# SCH_AVlabs_AV-GMK_MK_I_2024-01-18.net
KiCad netlist of a schematic drawn in EasyEDA
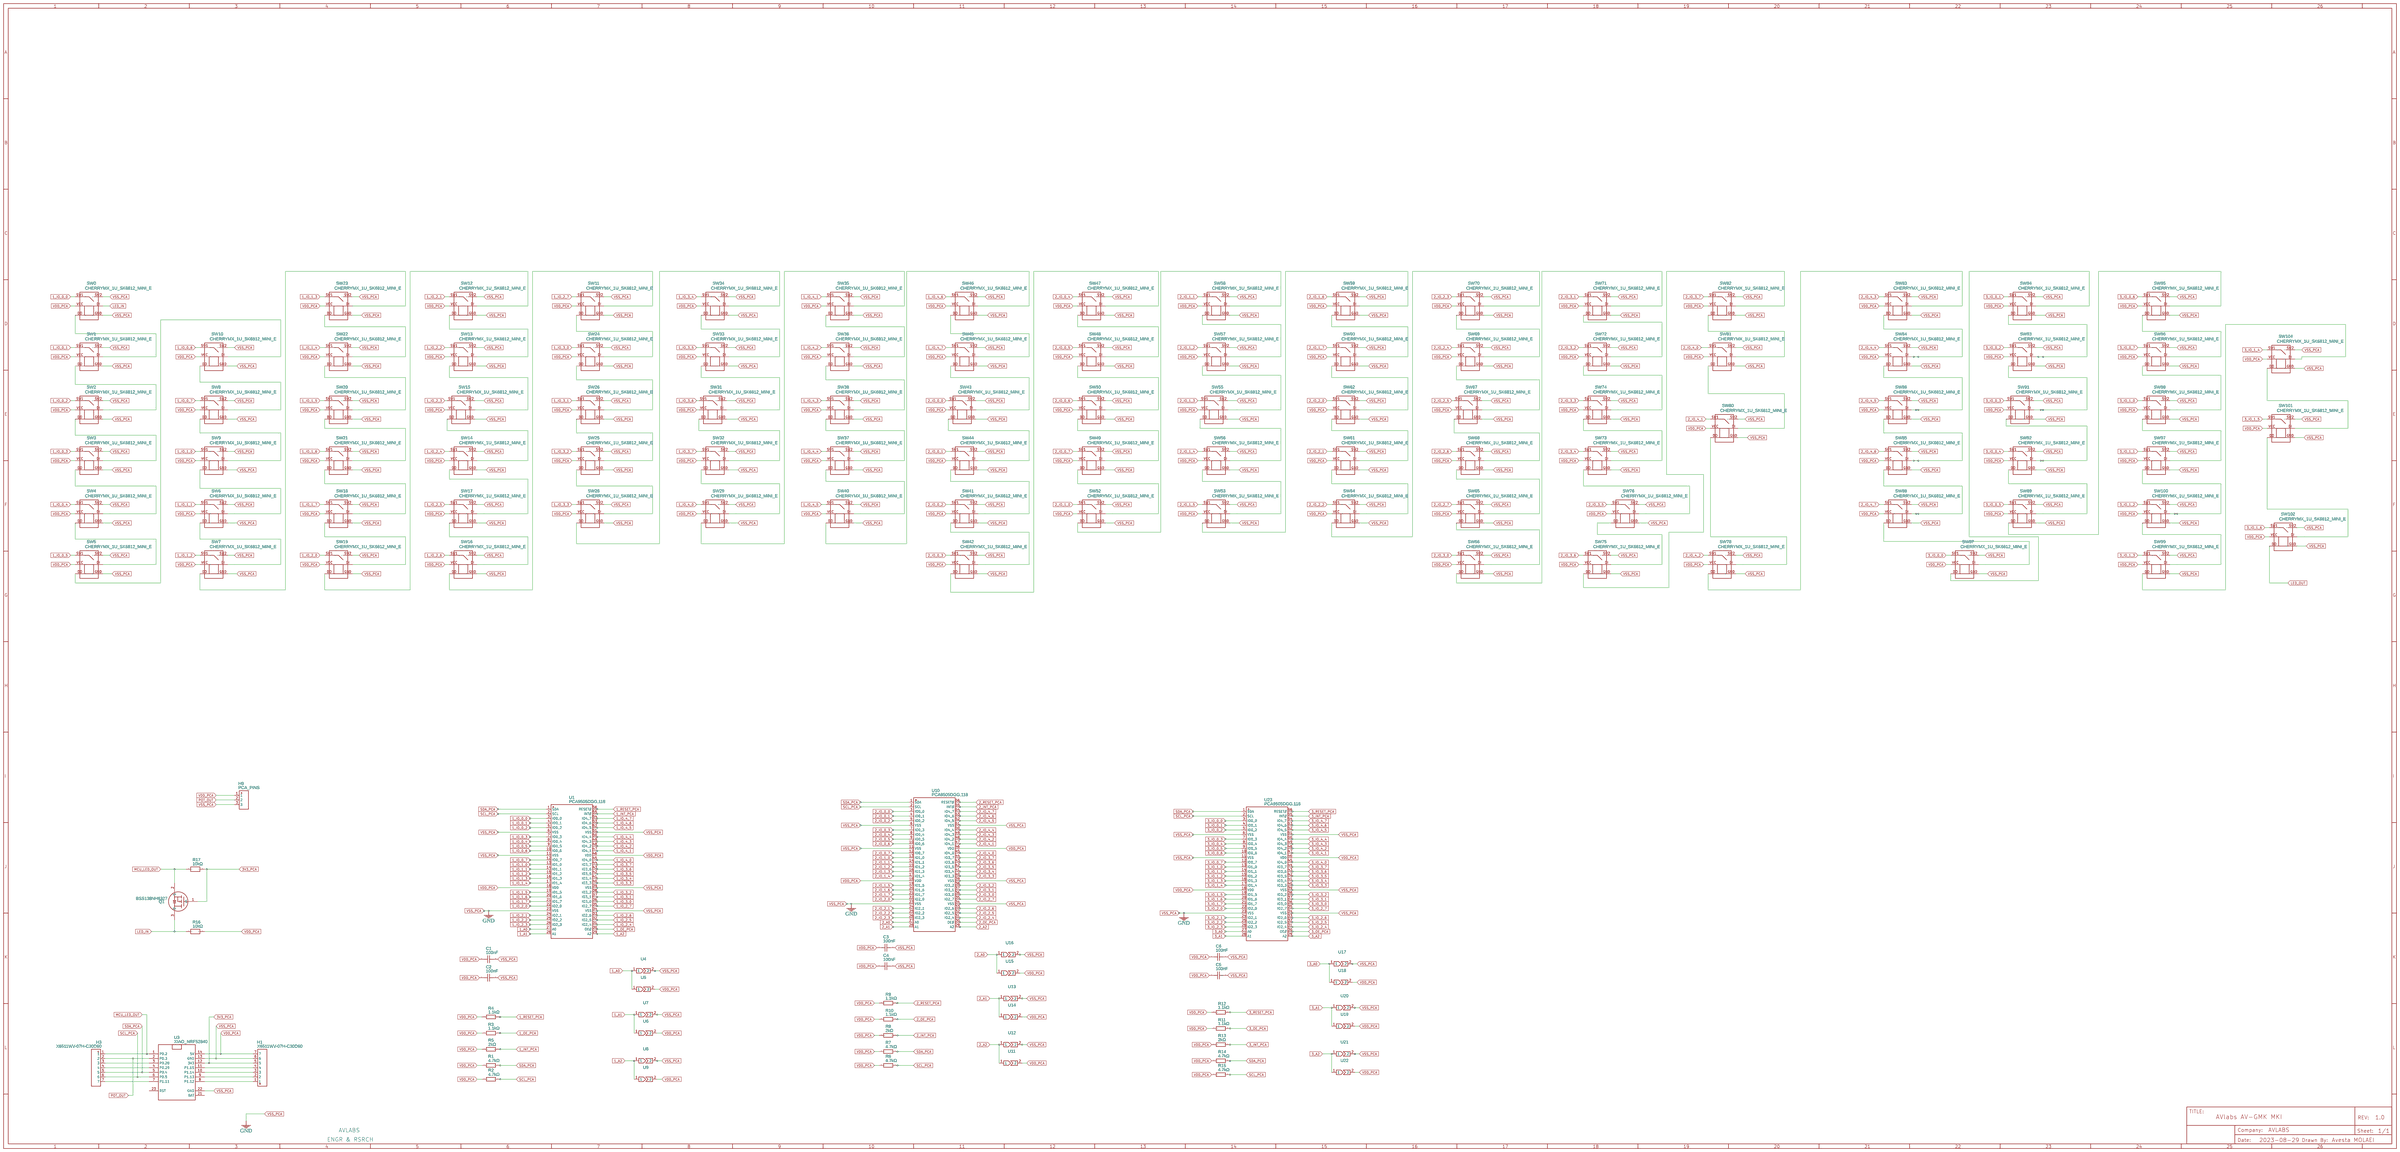
[diagram p0: schematic sheet]

(export (version "E")
  (design (tool "Eeschema 10.0.6"))
  (components
    (comp (ref "C1")
      (value "100nF")
      (fields
        (field (name "Manufacturer Part") "GRM21BR71H104KA01L")
        (field (name "Manufacturer") "muRata(村田)")
      )
      (libsource (lib "") (part "GRM21BR71H104KA01L"))
    )
    (comp (ref "C2")
      (value "100nF")
      (fields
        (field (name "Manufacturer Part") "GRM21BR71H104KA01L")
        (field (name "Manufacturer") "muRata(村田)")
      )
      (libsource (lib "") (part "GRM21BR71H104KA01L"))
    )
    (comp (ref "C3")
      (value "100nF")
      (fields
        (field (name "Manufacturer Part") "GRM21BR71H104KA01L")
        (field (name "Manufacturer") "muRata(村田)")
      )
      (libsource (lib "") (part "GRM21BR71H104KA01L"))
    )
    (comp (ref "C4")
      (value "100nF")
      (fields
        (field (name "Manufacturer Part") "GRM21BR71H104KA01L")
        (field (name "Manufacturer") "muRata(村田)")
      )
      (libsource (lib "") (part "GRM21BR71H104KA01L"))
    )
    (comp (ref "C5")
      (value "100nF")
      (fields
        (field (name "Manufacturer Part") "GRM21BR71H104KA01L")
        (field (name "Manufacturer") "muRata(村田)")
      )
      (libsource (lib "") (part "GRM21BR71H104KA01L"))
    )
    (comp (ref "C6")
      (value "100nF")
      (fields
        (field (name "Manufacturer Part") "GRM21BR71H104KA01L")
        (field (name "Manufacturer") "muRata(村田)")
      )
      (libsource (lib "") (part "GRM21BR71H104KA01L"))
    )
    (comp (ref "H1")
      (value "X6511WV-07H-C30D60")
      (fields (field (name "Manufacturer") "XKB Connectivity(中国星坤)"))
      (libsource (lib "") (part "X6511WV-07H-C30D60"))
    )
    (comp (ref "H3")
      (value "X6511WV-07H-C30D60")
      (fields (field (name "Manufacturer") "XKB Connectivity(中国星坤)"))
      (libsource (lib "") (part "X6511WV-07H-C30D60_1"))
    )
    (comp (ref "H9")
      (value "PCA_PINS")
      (fields
        (field (name "Manufacturer Part") "X6511WV-03H-C30D60")
        (field (name "Manufacturer") "XKB Connectivity(中国星坤)")
      )
      (libsource (lib "") (part "X6511WV-03H-C30D60"))
    )
    (comp (ref "Q1")
      (value "BSS138NH6327")
      (fields (field (name "Manufacturer") "Infineon(英飞凌)"))
      (libsource (lib "") (part "BSS138NH6327"))
    )
    (comp (ref "R1")
      (value "4.7kΩ")
      (fields (field (name "Manufacturer Part") "RN732ATTD4701B25") (field (name "Manufacturer") "KOA"))
      (libsource (lib "") (part "RN732ATTD4701B25"))
    )
    (comp (ref "R2")
      (value "4.7kΩ")
      (fields (field (name "Manufacturer Part") "RN732ATTD4701B25") (field (name "Manufacturer") "KOA"))
      (libsource (lib "") (part "RN732ATTD4701B25"))
    )
    (comp (ref "R3")
      (value "1.1kΩ")
      (fields (field (name "Manufacturer Part") "RN732ATTD1101B25") (field (name "Manufacturer") "KOA"))
      (libsource (lib "") (part "RN732ATTD1101B25"))
    )
    (comp (ref "R4")
      (value "1.1kΩ")
      (fields (field (name "Manufacturer Part") "RN732ATTD1101B25") (field (name "Manufacturer") "KOA"))
      (libsource (lib "") (part "RN732ATTD1101B25"))
    )
    (comp (ref "R5")
      (value "2kΩ")
      (fields (field (name "Manufacturer Part") "RN732ATTD2001B25") (field (name "Manufacturer") "KOA"))
      (libsource (lib "") (part "RN732ATTD2001B25"))
    )
    (comp (ref "R6")
      (value "4.7kΩ")
      (fields (field (name "Manufacturer Part") "RN732ATTD4701B25") (field (name "Manufacturer") "KOA"))
      (libsource (lib "") (part "RN732ATTD4701B25"))
    )
    (comp (ref "R7")
      (value "4.7kΩ")
      (fields (field (name "Manufacturer Part") "RN732ATTD4701B25") (field (name "Manufacturer") "KOA"))
      (libsource (lib "") (part "RN732ATTD4701B25"))
    )
    (comp (ref "R8")
      (value "2kΩ")
      (fields (field (name "Manufacturer Part") "RN732ATTD2001B25") (field (name "Manufacturer") "KOA"))
      (libsource (lib "") (part "RN732ATTD2001B25"))
    )
    (comp (ref "R9")
      (value "1.1kΩ")
      (fields (field (name "Manufacturer Part") "RN732ATTD1101B25") (field (name "Manufacturer") "KOA"))
      (libsource (lib "") (part "RN732ATTD1101B25"))
    )
    (comp (ref "R10")
      (value "1.1kΩ")
      (fields (field (name "Manufacturer Part") "RN732ATTD1101B25") (field (name "Manufacturer") "KOA"))
      (libsource (lib "") (part "RN732ATTD1101B25"))
    )
    (comp (ref "R11")
      (value "1.1kΩ")
      (fields (field (name "Manufacturer Part") "RN732ATTD1101B25") (field (name "Manufacturer") "KOA"))
      (libsource (lib "") (part "RN732ATTD1101B25"))
    )
    (comp (ref "R12")
      (value "1.1kΩ")
      (fields (field (name "Manufacturer Part") "RN732ATTD1101B25") (field (name "Manufacturer") "KOA"))
      (libsource (lib "") (part "RN732ATTD1101B25"))
    )
    (comp (ref "R13")
      (value "2kΩ")
      (fields (field (name "Manufacturer Part") "RN732ATTD2001B25") (field (name "Manufacturer") "KOA"))
      (libsource (lib "") (part "RN732ATTD2001B25"))
    )
    (comp (ref "R14")
      (value "4.7kΩ")
      (fields (field (name "Manufacturer Part") "RN732ATTD4701B25") (field (name "Manufacturer") "KOA"))
      (libsource (lib "") (part "RN732ATTD4701B25"))
    )
    (comp (ref "R15")
      (value "4.7kΩ")
      (fields (field (name "Manufacturer Part") "RN732ATTD4701B25") (field (name "Manufacturer") "KOA"))
      (libsource (lib "") (part "RN732ATTD4701B25"))
    )
    (comp (ref "R16")
      (value "10kΩ")
      (fields (field (name "Manufacturer Part") "RN732ATTD1002B10") (field (name "Manufacturer") "KOA"))
      (libsource (lib "") (part "RN732ATTD1002B10"))
    )
    (comp (ref "R17")
      (value "10kΩ")
      (fields (field (name "Manufacturer Part") "RN732ATTD1002B10") (field (name "Manufacturer") "KOA"))
      (libsource (lib "") (part "RN732ATTD1002B10"))
    )
    (comp (ref "SW0")
      (value "CHERRYMX_1U_SK6812_MINI_E")
      (libsource (lib "") (part "CHERRYMX_1U_SK6812_MINI_E"))
    )
    (comp (ref "SW1")
      (value "CHERRYMX_1U_SK6812_MINI_E")
      (libsource (lib "") (part "CHERRYMX_1U_SK6812_MINI_E"))
    )
    (comp (ref "SW2")
      (value "CHERRYMX_1U_SK6812_MINI_E")
      (libsource (lib "") (part "CHERRYMX_1U_SK6812_MINI_E"))
    )
    (comp (ref "SW3")
      (value "CHERRYMX_1U_SK6812_MINI_E")
      (libsource (lib "") (part "CHERRYMX_1U_SK6812_MINI_E"))
    )
    (comp (ref "SW4")
      (value "CHERRYMX_1U_SK6812_MINI_E")
      (libsource (lib "") (part "CHERRYMX_1U_SK6812_MINI_E"))
    )
    (comp (ref "SW5")
      (value "CHERRYMX_1U_SK6812_MINI_E")
      (libsource (lib "") (part "CHERRYMX_1U_SK6812_MINI_E"))
    )
    (comp (ref "SW6")
      (value "CHERRYMX_1U_SK6812_MINI_E")
      (libsource (lib "") (part "CHERRYMX_1U_SK6812_MINI_E"))
    )
    (comp (ref "SW7")
      (value "CHERRYMX_1U_SK6812_MINI_E")
      (libsource (lib "") (part "CHERRYMX_1U_SK6812_MINI_E"))
    )
    (comp (ref "SW8")
      (value "CHERRYMX_1U_SK6812_MINI_E")
      (libsource (lib "") (part "CHERRYMX_1U_SK6812_MINI_E"))
    )
    (comp (ref "SW9")
      (value "CHERRYMX_1U_SK6812_MINI_E")
      (libsource (lib "") (part "CHERRYMX_1U_SK6812_MINI_E"))
    )
    (comp (ref "SW10")
      (value "CHERRYMX_1U_SK6812_MINI_E")
      (libsource (lib "") (part "CHERRYMX_1U_SK6812_MINI_E"))
    )
    (comp (ref "SW11")
      (value "CHERRYMX_1U_SK6812_MINI_E")
      (libsource (lib "") (part "CHERRYMX_1U_SK6812_MINI_E"))
    )
    (comp (ref "SW12")
      (value "CHERRYMX_1U_SK6812_MINI_E")
      (libsource (lib "") (part "CHERRYMX_1U_SK6812_MINI_E"))
    )
    (comp (ref "SW13")
      (value "CHERRYMX_1U_SK6812_MINI_E")
      (libsource (lib "") (part "CHERRYMX_1U_SK6812_MINI_E"))
    )
    (comp (ref "SW14")
      (value "CHERRYMX_1U_SK6812_MINI_E")
      (libsource (lib "") (part "CHERRYMX_1U_SK6812_MINI_E"))
    )
    (comp (ref "SW15")
      (value "CHERRYMX_1U_SK6812_MINI_E")
      (libsource (lib "") (part "CHERRYMX_1U_SK6812_MINI_E"))
    )
    (comp (ref "SW16")
      (value "CHERRYMX_1U_SK6812_MINI_E")
      (libsource (lib "") (part "CHERRYMX_1U_SK6812_MINI_E"))
    )
    (comp (ref "SW17")
      (value "CHERRYMX_1U_SK6812_MINI_E")
      (libsource (lib "") (part "CHERRYMX_1U_SK6812_MINI_E"))
    )
    (comp (ref "SW18")
      (value "CHERRYMX_1U_SK6812_MINI_E")
      (libsource (lib "") (part "CHERRYMX_1U_SK6812_MINI_E"))
    )
    (comp (ref "SW19")
      (value "CHERRYMX_1U_SK6812_MINI_E")
      (libsource (lib "") (part "CHERRYMX_1U_SK6812_MINI_E"))
    )
    (comp (ref "SW20")
      (value "CHERRYMX_1U_SK6812_MINI_E")
      (libsource (lib "") (part "CHERRYMX_1U_SK6812_MINI_E"))
    )
    (comp (ref "SW21")
      (value "CHERRYMX_1U_SK6812_MINI_E")
      (libsource (lib "") (part "CHERRYMX_1U_SK6812_MINI_E"))
    )
    (comp (ref "SW22")
      (value "CHERRYMX_1U_SK6812_MINI_E")
      (libsource (lib "") (part "CHERRYMX_1U_SK6812_MINI_E"))
    )
    (comp (ref "SW23")
      (value "CHERRYMX_1U_SK6812_MINI_E")
      (libsource (lib "") (part "CHERRYMX_1U_SK6812_MINI_E"))
    )
    (comp (ref "SW24")
      (value "CHERRYMX_1U_SK6812_MINI_E")
      (libsource (lib "") (part "CHERRYMX_1U_SK6812_MINI_E"))
    )
    (comp (ref "SW25")
      (value "CHERRYMX_1U_SK6812_MINI_E")
      (libsource (lib "") (part "CHERRYMX_1U_SK6812_MINI_E"))
    )
    (comp (ref "SW26")
      (value "CHERRYMX_1U_SK6812_MINI_E")
      (libsource (lib "") (part "CHERRYMX_1U_SK6812_MINI_E"))
    )
    (comp (ref "SW28")
      (value "CHERRYMX_1U_SK6812_MINI_E")
      (libsource (lib "") (part "CHERRYMX_1U_SK6812_MINI_E"))
    )
    (comp (ref "SW29")
      (value "CHERRYMX_1U_SK6812_MINI_E")
      (libsource (lib "") (part "CHERRYMX_1U_SK6812_MINI_E"))
    )
    (comp (ref "SW31")
      (value "CHERRYMX_1U_SK6812_MINI_E")
      (libsource (lib "") (part "CHERRYMX_1U_SK6812_MINI_E"))
    )
    (comp (ref "SW32")
      (value "CHERRYMX_1U_SK6812_MINI_E")
      (libsource (lib "") (part "CHERRYMX_1U_SK6812_MINI_E"))
    )
    (comp (ref "SW33")
      (value "CHERRYMX_1U_SK6812_MINI_E")
      (libsource (lib "") (part "CHERRYMX_1U_SK6812_MINI_E"))
    )
    (comp (ref "SW34")
      (value "CHERRYMX_1U_SK6812_MINI_E")
      (libsource (lib "") (part "CHERRYMX_1U_SK6812_MINI_E"))
    )
    (comp (ref "SW35")
      (value "CHERRYMX_1U_SK6812_MINI_E")
      (libsource (lib "") (part "CHERRYMX_1U_SK6812_MINI_E"))
    )
    (comp (ref "SW36")
      (value "CHERRYMX_1U_SK6812_MINI_E")
      (libsource (lib "") (part "CHERRYMX_1U_SK6812_MINI_E"))
    )
    (comp (ref "SW37")
      (value "CHERRYMX_1U_SK6812_MINI_E")
      (libsource (lib "") (part "CHERRYMX_1U_SK6812_MINI_E"))
    )
    (comp (ref "SW38")
      (value "CHERRYMX_1U_SK6812_MINI_E")
      (libsource (lib "") (part "CHERRYMX_1U_SK6812_MINI_E"))
    )
    (comp (ref "SW40")
      (value "CHERRYMX_1U_SK6812_MINI_E")
      (libsource (lib "") (part "CHERRYMX_1U_SK6812_MINI_E"))
    )
    (comp (ref "SW41")
      (value "CHERRYMX_1U_SK6812_MINI_E")
      (libsource (lib "") (part "CHERRYMX_1U_SK6812_MINI_E"))
    )
    (comp (ref "SW42")
      (value "CHERRYMX_1U_SK6812_MINI_E")
      (libsource (lib "") (part "CHERRYMX_1U_SK6812_MINI_E"))
    )
    (comp (ref "SW43")
      (value "CHERRYMX_1U_SK6812_MINI_E")
      (libsource (lib "") (part "CHERRYMX_1U_SK6812_MINI_E"))
    )
    (comp (ref "SW44")
      (value "CHERRYMX_1U_SK6812_MINI_E")
      (libsource (lib "") (part "CHERRYMX_1U_SK6812_MINI_E"))
    )
    (comp (ref "SW45")
      (value "CHERRYMX_1U_SK6812_MINI_E")
      (libsource (lib "") (part "CHERRYMX_1U_SK6812_MINI_E"))
    )
    (comp (ref "SW46")
      (value "CHERRYMX_1U_SK6812_MINI_E")
      (libsource (lib "") (part "CHERRYMX_1U_SK6812_MINI_E"))
    )
    (comp (ref "SW47")
      (value "CHERRYMX_1U_SK6812_MINI_E")
      (libsource (lib "") (part "CHERRYMX_1U_SK6812_MINI_E"))
    )
    (comp (ref "SW48")
      (value "CHERRYMX_1U_SK6812_MINI_E")
      (libsource (lib "") (part "CHERRYMX_1U_SK6812_MINI_E"))
    )
    (comp (ref "SW49")
      (value "CHERRYMX_1U_SK6812_MINI_E")
      (libsource (lib "") (part "CHERRYMX_1U_SK6812_MINI_E"))
    )
    (comp (ref "SW50")
      (value "CHERRYMX_1U_SK6812_MINI_E")
      (libsource (lib "") (part "CHERRYMX_1U_SK6812_MINI_E"))
    )
    (comp (ref "SW52")
      (value "CHERRYMX_1U_SK6812_MINI_E")
      (libsource (lib "") (part "CHERRYMX_1U_SK6812_MINI_E"))
    )
    (comp (ref "SW53")
      (value "CHERRYMX_1U_SK6812_MINI_E")
      (libsource (lib "") (part "CHERRYMX_1U_SK6812_MINI_E"))
    )
    (comp (ref "SW55")
      (value "CHERRYMX_1U_SK6812_MINI_E")
      (libsource (lib "") (part "CHERRYMX_1U_SK6812_MINI_E"))
    )
    (comp (ref "SW56")
      (value "CHERRYMX_1U_SK6812_MINI_E")
      (libsource (lib "") (part "CHERRYMX_1U_SK6812_MINI_E"))
    )
    (comp (ref "SW57")
      (value "CHERRYMX_1U_SK6812_MINI_E")
      (libsource (lib "") (part "CHERRYMX_1U_SK6812_MINI_E"))
    )
    (comp (ref "SW58")
      (value "CHERRYMX_1U_SK6812_MINI_E")
      (libsource (lib "") (part "CHERRYMX_1U_SK6812_MINI_E"))
    )
    (comp (ref "SW59")
      (value "CHERRYMX_1U_SK6812_MINI_E")
      (libsource (lib "") (part "CHERRYMX_1U_SK6812_MINI_E"))
    )
    (comp (ref "SW60")
      (value "CHERRYMX_1U_SK6812_MINI_E")
      (libsource (lib "") (part "CHERRYMX_1U_SK6812_MINI_E"))
    )
    (comp (ref "SW61")
      (value "CHERRYMX_1U_SK6812_MINI_E")
      (libsource (lib "") (part "CHERRYMX_1U_SK6812_MINI_E"))
    )
    (comp (ref "SW62")
      (value "CHERRYMX_1U_SK6812_MINI_E")
      (libsource (lib "") (part "CHERRYMX_1U_SK6812_MINI_E"))
    )
    (comp (ref "SW64")
      (value "CHERRYMX_1U_SK6812_MINI_E")
      (libsource (lib "") (part "CHERRYMX_1U_SK6812_MINI_E"))
    )
    (comp (ref "SW65")
      (value "CHERRYMX_1U_SK6812_MINI_E")
      (libsource (lib "") (part "CHERRYMX_1U_SK6812_MINI_E"))
    )
    (comp (ref "SW66")
      (value "CHERRYMX_1U_SK6812_MINI_E")
      (libsource (lib "") (part "CHERRYMX_1U_SK6812_MINI_E"))
    )
    (comp (ref "SW67")
      (value "CHERRYMX_1U_SK6812_MINI_E")
      (libsource (lib "") (part "CHERRYMX_1U_SK6812_MINI_E"))
    )
    (comp (ref "SW68")
      (value "CHERRYMX_1U_SK6812_MINI_E")
      (libsource (lib "") (part "CHERRYMX_1U_SK6812_MINI_E"))
    )
    (comp (ref "SW69")
      (value "CHERRYMX_1U_SK6812_MINI_E")
      (libsource (lib "") (part "CHERRYMX_1U_SK6812_MINI_E"))
    )
    (comp (ref "SW70")
      (value "CHERRYMX_1U_SK6812_MINI_E")
      (libsource (lib "") (part "CHERRYMX_1U_SK6812_MINI_E"))
    )
    (comp (ref "SW71")
      (value "CHERRYMX_1U_SK6812_MINI_E")
      (libsource (lib "") (part "CHERRYMX_1U_SK6812_MINI_E"))
    )
    (comp (ref "SW72")
      (value "CHERRYMX_1U_SK6812_MINI_E")
      (libsource (lib "") (part "CHERRYMX_1U_SK6812_MINI_E"))
    )
    (comp (ref "SW73")
      (value "CHERRYMX_1U_SK6812_MINI_E")
      (libsource (lib "") (part "CHERRYMX_1U_SK6812_MINI_E"))
    )
    (comp (ref "SW74")
      (value "CHERRYMX_1U_SK6812_MINI_E")
      (libsource (lib "") (part "CHERRYMX_1U_SK6812_MINI_E"))
    )
    (comp (ref "SW75")
      (value "CHERRYMX_1U_SK6812_MINI_E")
      (libsource (lib "") (part "CHERRYMX_1U_SK6812_MINI_E"))
    )
    (comp (ref "SW76")
      (value "CHERRYMX_1U_SK6812_MINI_E")
      (libsource (lib "") (part "CHERRYMX_1U_SK6812_MINI_E"))
    )
    (comp (ref "SW78")
      (value "CHERRYMX_1U_SK6812_MINI_E")
      (libsource (lib "") (part "CHERRYMX_1U_SK6812_MINI_E"))
    )
    (comp (ref "SW80")
      (value "CHERRYMX_1U_SK6812_MINI_E")
      (libsource (lib "") (part "CHERRYMX_1U_SK6812_MINI_E"))
    )
    (comp (ref "SW81")
      (value "CHERRYMX_1U_SK6812_MINI_E")
      (libsource (lib "") (part "CHERRYMX_1U_SK6812_MINI_E"))
    )
    (comp (ref "SW82")
      (value "CHERRYMX_1U_SK6812_MINI_E")
      (libsource (lib "") (part "CHERRYMX_1U_SK6812_MINI_E"))
    )
    (comp (ref "SW83")
      (value "CHERRYMX_1U_SK6812_MINI_E")
      (libsource (lib "") (part "CHERRYMX_1U_SK6812_MINI_E"))
    )
    (comp (ref "SW84")
      (value "CHERRYMX_1U_SK6812_MINI_E")
      (libsource (lib "") (part "CHERRYMX_1U_SK6812_MINI_E"))
    )
    (comp (ref "SW85")
      (value "CHERRYMX_1U_SK6812_MINI_E")
      (libsource (lib "") (part "CHERRYMX_1U_SK6812_MINI_E"))
    )
    (comp (ref "SW86")
      (value "CHERRYMX_1U_SK6812_MINI_E")
      (libsource (lib "") (part "CHERRYMX_1U_SK6812_MINI_E"))
    )
    (comp (ref "SW87")
      (value "CHERRYMX_1U_SK6812_MINI_E")
      (libsource (lib "") (part "CHERRYMX_1U_SK6812_MINI_E"))
    )
    (comp (ref "SW88")
      (value "CHERRYMX_1U_SK6812_MINI_E")
      (libsource (lib "") (part "CHERRYMX_1U_SK6812_MINI_E"))
    )
    (comp (ref "SW89")
      (value "CHERRYMX_1U_SK6812_MINI_E")
      (libsource (lib "") (part "CHERRYMX_1U_SK6812_MINI_E"))
    )
    (comp (ref "SW91")
      (value "CHERRYMX_1U_SK6812_MINI_E")
      (libsource (lib "") (part "CHERRYMX_1U_SK6812_MINI_E"))
    )
    (comp (ref "SW92")
      (value "CHERRYMX_1U_SK6812_MINI_E")
      (libsource (lib "") (part "CHERRYMX_1U_SK6812_MINI_E"))
    )
    (comp (ref "SW93")
      (value "CHERRYMX_1U_SK6812_MINI_E")
      (libsource (lib "") (part "CHERRYMX_1U_SK6812_MINI_E"))
    )
    (comp (ref "SW94")
      (value "CHERRYMX_1U_SK6812_MINI_E")
      (libsource (lib "") (part "CHERRYMX_1U_SK6812_MINI_E"))
    )
    (comp (ref "SW95")
      (value "CHERRYMX_1U_SK6812_MINI_E")
      (libsource (lib "") (part "CHERRYMX_1U_SK6812_MINI_E"))
    )
    (comp (ref "SW96")
      (value "CHERRYMX_1U_SK6812_MINI_E")
      (libsource (lib "") (part "CHERRYMX_1U_SK6812_MINI_E"))
    )
    (comp (ref "SW97")
      (value "CHERRYMX_1U_SK6812_MINI_E")
      (libsource (lib "") (part "CHERRYMX_1U_SK6812_MINI_E"))
    )
    (comp (ref "SW98")
      (value "CHERRYMX_1U_SK6812_MINI_E")
      (libsource (lib "") (part "CHERRYMX_1U_SK6812_MINI_E"))
    )
    (comp (ref "SW99")
      (value "CHERRYMX_1U_SK6812_MINI_E")
      (libsource (lib "") (part "CHERRYMX_1U_SK6812_MINI_E"))
    )
    (comp (ref "SW100")
      (value "CHERRYMX_1U_SK6812_MINI_E")
      (libsource (lib "") (part "CHERRYMX_1U_SK6812_MINI_E"))
    )
    (comp (ref "SW101")
      (value "CHERRYMX_1U_SK6812_MINI_E")
      (libsource (lib "") (part "CHERRYMX_1U_SK6812_MINI_E"))
    )
    (comp (ref "SW102")
      (value "CHERRYMX_1U_SK6812_MINI_E")
      (libsource (lib "") (part "CHERRYMX_1U_SK6812_MINI_E"))
    )
    (comp (ref "SW104")
      (value "CHERRYMX_1U_SK6812_MINI_E")
      (libsource (lib "") (part "CHERRYMX_1U_SK6812_MINI_E"))
    )
    (comp (ref "U1")
      (value "PCA9505DGG,118")
      (fields (field (name "Manufacturer") "NXP(恩智浦)"))
      (libsource (lib "") (part "PCA9505DGG,118"))
    )
    (comp (ref "U3") (value "XIAO_NRF52840") (libsource (lib "") (part "XIAO_NRF52840")))
    (comp (ref "U4") (value "beautiful-solderbridge") (libsource (lib "") (part "beautiful-solderbridge")))
    (comp (ref "U5") (value "beautiful-solderbridge") (libsource (lib "") (part "beautiful-solderbridge")))
    (comp (ref "U6") (value "beautiful-solderbridge") (libsource (lib "") (part "beautiful-solderbridge")))
    (comp (ref "U7") (value "beautiful-solderbridge") (libsource (lib "") (part "beautiful-solderbridge")))
    (comp (ref "U8") (value "beautiful-solderbridge") (libsource (lib "") (part "beautiful-solderbridge")))
    (comp (ref "U9") (value "beautiful-solderbridge") (libsource (lib "") (part "beautiful-solderbridge")))
    (comp (ref "U10")
      (value "PCA9505DGG,118")
      (fields (field (name "Manufacturer") "NXP(恩智浦)"))
      (libsource (lib "") (part "PCA9505DGG,118"))
    )
    (comp (ref "U11") (value "beautiful-solderbridge") (libsource (lib "") (part "beautiful-solderbridge")))
    (comp (ref "U12") (value "beautiful-solderbridge") (libsource (lib "") (part "beautiful-solderbridge")))
    (comp (ref "U13") (value "beautiful-solderbridge") (libsource (lib "") (part "beautiful-solderbridge")))
    (comp (ref "U14") (value "beautiful-solderbridge") (libsource (lib "") (part "beautiful-solderbridge")))
    (comp (ref "U15") (value "beautiful-solderbridge") (libsource (lib "") (part "beautiful-solderbridge")))
    (comp (ref "U16") (value "beautiful-solderbridge") (libsource (lib "") (part "beautiful-solderbridge")))
    (comp (ref "U17") (value "beautiful-solderbridge") (libsource (lib "") (part "beautiful-solderbridge")))
    (comp (ref "U18") (value "beautiful-solderbridge") (libsource (lib "") (part "beautiful-solderbridge")))
    (comp (ref "U19") (value "beautiful-solderbridge") (libsource (lib "") (part "beautiful-solderbridge")))
    (comp (ref "U20") (value "beautiful-solderbridge") (libsource (lib "") (part "beautiful-solderbridge")))
    (comp (ref "U21") (value "beautiful-solderbridge") (libsource (lib "") (part "beautiful-solderbridge")))
    (comp (ref "U22") (value "beautiful-solderbridge") (libsource (lib "") (part "beautiful-solderbridge")))
    (comp (ref "U23")
      (value "PCA9505DGG,118")
      (fields (field (name "Manufacturer") "NXP(恩智浦)"))
      (libsource (lib "") (part "PCA9505DGG,118"))
    )
  )
  (nets
    (net (code "1") (name "1_A0") (class "Default")
      (node (ref "U1") (pin "27") (pinfunction "A0_27") (pintype "unspecified"))
      (node (ref "U4") (pin "1") (pinfunction "1_1") (pintype "unspecified"))
      (node (ref "U5") (pin "1") (pinfunction "1_1") (pintype "unspecified"))
    )
    (net (code "2") (name "1_A1") (class "Default")
      (node (ref "U1") (pin "28") (pinfunction "A1_28") (pintype "unspecified"))
      (node (ref "U6") (pin "1") (pinfunction "1_1") (pintype "unspecified"))
      (node (ref "U7") (pin "1") (pinfunction "1_1") (pintype "unspecified"))
    )
    (net (code "3") (name "1_A2") (class "Default")
      (node (ref "U1") (pin "29") (pinfunction "A2_29") (pintype "unspecified"))
      (node (ref "U8") (pin "1") (pinfunction "1_1") (pintype "unspecified"))
      (node (ref "U9") (pin "1") (pinfunction "1_1") (pintype "unspecified"))
    )
    (net (code "4") (name "1_INT_PCA") (class "Default")
      (node (ref "R5") (pin "2") (pinfunction "2_2") (pintype "unspecified"))
      (node (ref "U1") (pin "55") (pinfunction "INT#_55") (pintype "unspecified"))
    )
    (net (code "5") (name "1_IO_0_0") (class "Default")
      (node (ref "SW0") (pin "SW1") (pinfunction "SW1_SW1") (pintype "unspecified"))
      (node (ref "U1") (pin "3") (pinfunction "IO0_0_3") (pintype "unspecified"))
    )
    (net (code "6") (name "1_IO_0_1") (class "Default")
      (node (ref "SW1") (pin "SW1") (pinfunction "SW1_SW1") (pintype "unspecified"))
      (node (ref "U1") (pin "4") (pinfunction "IO0_1_4") (pintype "unspecified"))
    )
    (net (code "7") (name "1_IO_0_2") (class "Default")
      (node (ref "SW2") (pin "SW1") (pinfunction "SW1_SW1") (pintype "unspecified"))
      (node (ref "U1") (pin "5") (pinfunction "IO0_2_5") (pintype "unspecified"))
    )
    (net (code "8") (name "1_IO_0_3") (class "Default")
      (node (ref "SW3") (pin "SW1") (pinfunction "SW1_SW1") (pintype "unspecified"))
      (node (ref "U1") (pin "7") (pinfunction "IO0_3_7") (pintype "unspecified"))
    )
    (net (code "9") (name "1_IO_0_4") (class "Default")
      (node (ref "SW4") (pin "SW1") (pinfunction "SW1_SW1") (pintype "unspecified"))
      (node (ref "U1") (pin "8") (pinfunction "IO0_4_8") (pintype "unspecified"))
    )
    (net (code "10") (name "1_IO_0_5") (class "Default")
      (node (ref "SW5") (pin "SW1") (pinfunction "SW1_SW1") (pintype "unspecified"))
      (node (ref "U1") (pin "9") (pinfunction "IO0_5_9") (pintype "unspecified"))
    )
    (net (code "11") (name "1_IO_0_6") (class "Default")
      (node (ref "SW10") (pin "SW1") (pinfunction "SW1_SW1") (pintype "unspecified"))
      (node (ref "U1") (pin "10") (pinfunction "IO0_6_10") (pintype "unspecified"))
    )
    (net (code "12") (name "1_IO_0_7") (class "Default")
      (node (ref "SW8") (pin "SW1") (pinfunction "SW1_SW1") (pintype "unspecified"))
      (node (ref "U1") (pin "12") (pinfunction "IO0_7_12") (pintype "unspecified"))
    )
    (net (code "13") (name "1_IO_1_0") (class "Default")
      (node (ref "SW9") (pin "SW1") (pinfunction "SW1_SW1") (pintype "unspecified"))
      (node (ref "U1") (pin "13") (pinfunction "IO1_0_13") (pintype "unspecified"))
    )
    (net (code "14") (name "1_IO_1_1") (class "Default")
      (node (ref "SW6") (pin "SW1") (pinfunction "SW1_SW1") (pintype "unspecified"))
      (node (ref "U1") (pin "14") (pinfunction "IO1_1_14") (pintype "unspecified"))
    )
    (net (code "15") (name "1_IO_1_2") (class "Default")
      (node (ref "SW7") (pin "SW1") (pinfunction "SW1_SW1") (pintype "unspecified"))
      (node (ref "U1") (pin "15") (pinfunction "IO1_2_15") (pintype "unspecified"))
    )
    (net (code "16") (name "1_IO_1_3") (class "Default")
      (node (ref "SW23") (pin "SW1") (pinfunction "SW1_SW1") (pintype "unspecified"))
      (node (ref "U1") (pin "16") (pinfunction "IO1_3_16") (pintype "unspecified"))
    )
    (net (code "17") (name "1_IO_1_4") (class "Default")
      (node (ref "SW22") (pin "SW1") (pinfunction "SW1_SW1") (pintype "unspecified"))
      (node (ref "U1") (pin "17") (pinfunction "IO1_4_17") (pintype "unspecified"))
    )
    (net (code "18") (name "1_IO_1_5") (class "Default")
      (node (ref "SW20") (pin "SW1") (pinfunction "SW1_SW1") (pintype "unspecified"))
      (node (ref "U1") (pin "19") (pinfunction "IO1_5_19") (pintype "unspecified"))
    )
    (net (code "19") (name "1_IO_1_6") (class "Default")
      (node (ref "SW21") (pin "SW1") (pinfunction "SW1_SW1") (pintype "unspecified"))
      (node (ref "U1") (pin "20") (pinfunction "IO1_6_20") (pintype "unspecified"))
    )
    (net (code "20") (name "1_IO_1_7") (class "Default")
      (node (ref "SW18") (pin "SW1") (pinfunction "SW1_SW1") (pintype "unspecified"))
      (node (ref "U1") (pin "21") (pinfunction "IO1_7_21") (pintype "unspecified"))
    )
    (net (code "21") (name "1_IO_2_0") (class "Default")
      (node (ref "SW19") (pin "SW1") (pinfunction "SW1_SW1") (pintype "unspecified"))
      (node (ref "U1") (pin "22") (pinfunction "IO2_0_22") (pintype "unspecified"))
    )
    (net (code "22") (name "1_IO_2_1") (class "Default")
      (node (ref "SW12") (pin "SW1") (pinfunction "SW1_SW1") (pintype "unspecified"))
      (node (ref "U1") (pin "24") (pinfunction "IO2_1_24") (pintype "unspecified"))
    )
    (net (code "23") (name "1_IO_2_2") (class "Default")
      (node (ref "SW13") (pin "SW1") (pinfunction "SW1_SW1") (pintype "unspecified"))
      (node (ref "U1") (pin "25") (pinfunction "IO2_2_25") (pintype "unspecified"))
    )
    (net (code "24") (name "1_IO_2_3") (class "Default")
      (node (ref "SW15") (pin "SW1") (pinfunction "SW1_SW1") (pintype "unspecified"))
      (node (ref "U1") (pin "26") (pinfunction "IO2_3_26") (pintype "unspecified"))
    )
    (net (code "25") (name "1_IO_2_4") (class "Default")
      (node (ref "SW14") (pin "SW1") (pinfunction "SW1_SW1") (pintype "unspecified"))
      (node (ref "U1") (pin "31") (pinfunction "IO2_4_31") (pintype "unspecified"))
    )
    (net (code "26") (name "1_IO_2_5") (class "Default")
      (node (ref "SW17") (pin "SW1") (pinfunction "SW1_SW1") (pintype "unspecified"))
      (node (ref "U1") (pin "32") (pinfunction "IO2_5_32") (pintype "unspecified"))
    )
    (net (code "27") (name "1_IO_2_6") (class "Default")
      (node (ref "SW16") (pin "SW1") (pinfunction "SW1_SW1") (pintype "unspecified"))
      (node (ref "U1") (pin "33") (pinfunction "IO2_6_33") (pintype "unspecified"))
    )
    (net (code "28") (name "1_IO_2_7") (class "Default")
      (node (ref "SW11") (pin "SW1") (pinfunction "SW1_SW1") (pintype "unspecified"))
      (node (ref "U1") (pin "35") (pinfunction "IO2_7_35") (pintype "unspecified"))
    )
    (net (code "29") (name "1_IO_3_0") (class "Default")
      (node (ref "SW24") (pin "SW1") (pinfunction "SW1_SW1") (pintype "unspecified"))
      (node (ref "U1") (pin "36") (pinfunction "IO3_0_36") (pintype "unspecified"))
    )
    (net (code "30") (name "1_IO_3_1") (class "Default")
      (node (ref "SW26") (pin "SW1") (pinfunction "SW1_SW1") (pintype "unspecified"))
      (node (ref "U1") (pin "37") (pinfunction "IO3_1_37") (pintype "unspecified"))
    )
    (net (code "31") (name "1_IO_3_2") (class "Default")
      (node (ref "SW25") (pin "SW1") (pinfunction "SW1_SW1") (pintype "unspecified"))
      (node (ref "U1") (pin "38") (pinfunction "IO3_2_38") (pintype "unspecified"))
    )
    (net (code "32") (name "1_IO_3_3") (class "Default")
      (node (ref "SW28") (pin "SW1") (pinfunction "SW1_SW1") (pintype "unspecified"))
      (node (ref "U1") (pin "40") (pinfunction "IO3_3_40") (pintype "unspecified"))
    )
    (net (code "33") (name "1_IO_3_4") (class "Default")
      (node (ref "SW34") (pin "SW1") (pinfunction "SW1_SW1") (pintype "unspecified"))
      (node (ref "U1") (pin "41") (pinfunction "IO3_4_41") (pintype "unspecified"))
    )
    (net (code "34") (name "1_IO_3_5") (class "Default")
      (node (ref "SW33") (pin "SW1") (pinfunction "SW1_SW1") (pintype "unspecified"))
      (node (ref "U1") (pin "42") (pinfunction "IO3_5_42") (pintype "unspecified"))
    )
    (net (code "35") (name "1_IO_3_6") (class "Default")
      (node (ref "SW31") (pin "SW1") (pinfunction "SW1_SW1") (pintype "unspecified"))
      (node (ref "U1") (pin "43") (pinfunction "IO3_6_43") (pintype "unspecified"))
    )
    (net (code "36") (name "1_IO_3_7") (class "Default")
      (node (ref "SW32") (pin "SW1") (pinfunction "SW1_SW1") (pintype "unspecified"))
      (node (ref "U1") (pin "44") (pinfunction "IO3_7_44") (pintype "unspecified"))
    )
    (net (code "37") (name "1_IO_4_0") (class "Default")
      (node (ref "SW29") (pin "SW1") (pinfunction "SW1_SW1") (pintype "unspecified"))
      (node (ref "U1") (pin "45") (pinfunction "IO4_0_45") (pintype "unspecified"))
    )
    (net (code "38") (name "1_IO_4_1") (class "Default")
      (node (ref "SW35") (pin "SW1") (pinfunction "SW1_SW1") (pintype "unspecified"))
      (node (ref "U1") (pin "47") (pinfunction "IO4_1_47") (pintype "unspecified"))
    )
    (net (code "39") (name "1_IO_4_2") (class "Default")
      (node (ref "SW36") (pin "SW1") (pinfunction "SW1_SW1") (pintype "unspecified"))
      (node (ref "U1") (pin "48") (pinfunction "IO4_2_48") (pintype "unspecified"))
    )
    (net (code "40") (name "1_IO_4_3") (class "Default")
      (node (ref "SW38") (pin "SW1") (pinfunction "SW1_SW1") (pintype "unspecified"))
      (node (ref "U1") (pin "49") (pinfunction "IO4_3_49") (pintype "unspecified"))
    )
    (net (code "41") (name "1_IO_4_4") (class "Default")
      (node (ref "SW37") (pin "SW1") (pinfunction "SW1_SW1") (pintype "unspecified"))
      (node (ref "U1") (pin "50") (pinfunction "IO4_4_50") (pintype "unspecified"))
    )
    (net (code "42") (name "1_IO_4_5") (class "Default")
      (node (ref "SW40") (pin "SW1") (pinfunction "SW1_SW1") (pintype "unspecified"))
      (node (ref "U1") (pin "52") (pinfunction "IO4_5_52") (pintype "unspecified"))
    )
    (net (code "43") (name "1_IO_4_6") (class "Default")
      (node (ref "SW46") (pin "SW1") (pinfunction "SW1_SW1") (pintype "unspecified"))
      (node (ref "U1") (pin "53") (pinfunction "IO4_6_53") (pintype "unspecified"))
    )
    (net (code "44") (name "1_IO_4_7") (class "Default")
      (node (ref "SW45") (pin "SW1") (pinfunction "SW1_SW1") (pintype "unspecified"))
      (node (ref "U1") (pin "54") (pinfunction "IO4_7_54") (pintype "unspecified"))
    )
    (net (code "45") (name "1_OE_PCA") (class "Default")
      (node (ref "R3") (pin "2") (pinfunction "2_2") (pintype "unspecified"))
      (node (ref "U1") (pin "30") (pinfunction "OE#_30") (pintype "unspecified"))
    )
    (net (code "46") (name "1_RESET_PCA") (class "Default")
      (node (ref "R4") (pin "2") (pinfunction "2_2") (pintype "unspecified"))
      (node (ref "U1") (pin "56") (pinfunction "RESET#_56") (pintype "unspecified"))
    )
    (net (code "47") (name "2_A0") (class "Default")
      (node (ref "U10") (pin "27") (pinfunction "A0_27") (pintype "unspecified"))
      (node (ref "U15") (pin "1") (pinfunction "1_1") (pintype "unspecified"))
      (node (ref "U16") (pin "1") (pinfunction "1_1") (pintype "unspecified"))
    )
    (net (code "48") (name "2_A1") (class "Default")
      (node (ref "U10") (pin "28") (pinfunction "A1_28") (pintype "unspecified"))
      (node (ref "U13") (pin "1") (pinfunction "1_1") (pintype "unspecified"))
      (node (ref "U14") (pin "1") (pinfunction "1_1") (pintype "unspecified"))
    )
    (net (code "49") (name "2_A2") (class "Default")
      (node (ref "U10") (pin "29") (pinfunction "A2_29") (pintype "unspecified"))
      (node (ref "U11") (pin "1") (pinfunction "1_1") (pintype "unspecified"))
      (node (ref "U12") (pin "1") (pinfunction "1_1") (pintype "unspecified"))
    )
    (net (code "50") (name "2_INT_PCA") (class "Default")
      (node (ref "R8") (pin "2") (pinfunction "2_2") (pintype "unspecified"))
      (node (ref "U10") (pin "55") (pinfunction "INT#_55") (pintype "unspecified"))
    )
    (net (code "51") (name "2_IO_0_0") (class "Default")
      (node (ref "SW43") (pin "SW1") (pinfunction "SW1_SW1") (pintype "unspecified"))
      (node (ref "U10") (pin "3") (pinfunction "IO0_0_3") (pintype "unspecified"))
    )
    (net (code "52") (name "2_IO_0_1") (class "Default")
      (node (ref "SW44") (pin "SW1") (pinfunction "SW1_SW1") (pintype "unspecified"))
      (node (ref "U10") (pin "4") (pinfunction "IO0_1_4") (pintype "unspecified"))
    )
    (net (code "53") (name "2_IO_0_2") (class "Default")
      (node (ref "SW41") (pin "SW1") (pinfunction "SW1_SW1") (pintype "unspecified"))
      (node (ref "U10") (pin "5") (pinfunction "IO0_2_5") (pintype "unspecified"))
    )
    (net (code "54") (name "2_IO_0_3") (class "Default")
      (node (ref "SW42") (pin "SW1") (pinfunction "SW1_SW1") (pintype "unspecified"))
      (node (ref "U10") (pin "7") (pinfunction "IO0_3_7") (pintype "unspecified"))
    )
    (net (code "55") (name "2_IO_0_4") (class "Default")
      (node (ref "SW47") (pin "SW1") (pinfunction "SW1_SW1") (pintype "unspecified"))
      (node (ref "U10") (pin "8") (pinfunction "IO0_4_8") (pintype "unspecified"))
    )
    (net (code "56") (name "2_IO_0_5") (class "Default")
      (node (ref "SW48") (pin "SW1") (pinfunction "SW1_SW1") (pintype "unspecified"))
      (node (ref "U10") (pin "9") (pinfunction "IO0_5_9") (pintype "unspecified"))
    )
    (net (code "57") (name "2_IO_0_6") (class "Default")
      (node (ref "SW50") (pin "SW1") (pinfunction "SW1_SW1") (pintype "unspecified"))
      (node (ref "U10") (pin "10") (pinfunction "IO0_6_10") (pintype "unspecified"))
    )
    (net (code "58") (name "2_IO_0_7") (class "Default")
      (node (ref "SW49") (pin "SW1") (pinfunction "SW1_SW1") (pintype "unspecified"))
      (node (ref "U10") (pin "12") (pinfunction "IO0_7_12") (pintype "unspecified"))
    )
    (net (code "59") (name "2_IO_1_0") (class "Default")
      (node (ref "SW52") (pin "SW1") (pinfunction "SW1_SW1") (pintype "unspecified"))
      (node (ref "U10") (pin "13") (pinfunction "IO1_0_13") (pintype "unspecified"))
    )
    (net (code "60") (name "2_IO_1_1") (class "Default")
      (node (ref "SW58") (pin "SW1") (pinfunction "SW1_SW1") (pintype "unspecified"))
      (node (ref "U10") (pin "14") (pinfunction "IO1_1_14") (pintype "unspecified"))
    )
    (net (code "61") (name "2_IO_1_2") (class "Default")
      (node (ref "SW57") (pin "SW1") (pinfunction "SW1_SW1") (pintype "unspecified"))
      (node (ref "U10") (pin "15") (pinfunction "IO1_2_15") (pintype "unspecified"))
    )
    (net (code "62") (name "2_IO_1_3") (class "Default")
      (node (ref "SW55") (pin "SW1") (pinfunction "SW1_SW1") (pintype "unspecified"))
      (node (ref "U10") (pin "16") (pinfunction "IO1_3_16") (pintype "unspecified"))
    )
    (net (code "63") (name "2_IO_1_4") (class "Default")
      (node (ref "SW56") (pin "SW1") (pinfunction "SW1_SW1") (pintype "unspecified"))
      (node (ref "U10") (pin "17") (pinfunction "IO1_4_17") (pintype "unspecified"))
    )
    (net (code "64") (name "2_IO_1_5") (class "Default")
      (node (ref "SW53") (pin "SW1") (pinfunction "SW1_SW1") (pintype "unspecified"))
      (node (ref "U10") (pin "19") (pinfunction "IO1_5_19") (pintype "unspecified"))
    )
    (net (code "65") (name "2_IO_1_6") (class "Default")
      (node (ref "SW59") (pin "SW1") (pinfunction "SW1_SW1") (pintype "unspecified"))
      (node (ref "U10") (pin "20") (pinfunction "IO1_6_20") (pintype "unspecified"))
    )
    (net (code "66") (name "2_IO_1_7") (class "Default")
      (node (ref "SW60") (pin "SW1") (pinfunction "SW1_SW1") (pintype "unspecified"))
      (node (ref "U10") (pin "21") (pinfunction "IO1_7_21") (pintype "unspecified"))
    )
    (net (code "67") (name "2_IO_2_0") (class "Default")
      (node (ref "SW62") (pin "SW1") (pinfunction "SW1_SW1") (pintype "unspecified"))
      (node (ref "U10") (pin "22") (pinfunction "IO2_0_22") (pintype "unspecified"))
    )
    (net (code "68") (name "2_IO_2_1") (class "Default")
      (node (ref "SW61") (pin "SW1") (pinfunction "SW1_SW1") (pintype "unspecified"))
      (node (ref "U10") (pin "24") (pinfunction "IO2_1_24") (pintype "unspecified"))
    )
    (net (code "69") (name "2_IO_2_2") (class "Default")
      (node (ref "SW64") (pin "SW1") (pinfunction "SW1_SW1") (pintype "unspecified"))
      (node (ref "U10") (pin "25") (pinfunction "IO2_2_25") (pintype "unspecified"))
    )
    (net (code "70") (name "2_IO_2_3") (class "Default")
      (node (ref "SW70") (pin "SW1") (pinfunction "SW1_SW1") (pintype "unspecified"))
      (node (ref "U10") (pin "26") (pinfunction "IO2_3_26") (pintype "unspecified"))
    )
    (net (code "71") (name "2_IO_2_4") (class "Default")
      (node (ref "SW69") (pin "SW1") (pinfunction "SW1_SW1") (pintype "unspecified"))
      (node (ref "U10") (pin "31") (pinfunction "IO2_4_31") (pintype "unspecified"))
    )
    (net (code "72") (name "2_IO_2_5") (class "Default")
      (node (ref "SW67") (pin "SW1") (pinfunction "SW1_SW1") (pintype "unspecified"))
      (node (ref "U10") (pin "32") (pinfunction "IO2_5_32") (pintype "unspecified"))
    )
    (net (code "73") (name "2_IO_2_6") (class "Default")
      (node (ref "SW68") (pin "SW1") (pinfunction "SW1_SW1") (pintype "unspecified"))
      (node (ref "U10") (pin "33") (pinfunction "IO2_6_33") (pintype "unspecified"))
    )
    (net (code "74") (name "2_IO_2_7") (class "Default")
      (node (ref "SW65") (pin "SW1") (pinfunction "SW1_SW1") (pintype "unspecified"))
      (node (ref "U10") (pin "35") (pinfunction "IO2_7_35") (pintype "unspecified"))
    )
    (net (code "75") (name "2_IO_3_0") (class "Default")
      (node (ref "SW66") (pin "SW1") (pinfunction "SW1_SW1") (pintype "unspecified"))
      (node (ref "U10") (pin "36") (pinfunction "IO3_0_36") (pintype "unspecified"))
    )
    (net (code "76") (name "2_IO_3_1") (class "Default")
      (node (ref "SW71") (pin "SW1") (pinfunction "SW1_SW1") (pintype "unspecified"))
      (node (ref "U10") (pin "37") (pinfunction "IO3_1_37") (pintype "unspecified"))
    )
    (net (code "77") (name "2_IO_3_2") (class "Default")
      (node (ref "SW72") (pin "SW1") (pinfunction "SW1_SW1") (pintype "unspecified"))
      (node (ref "U10") (pin "38") (pinfunction "IO3_2_38") (pintype "unspecified"))
    )
    (net (code "78") (name "2_IO_3_3") (class "Default")
      (node (ref "SW74") (pin "SW1") (pinfunction "SW1_SW1") (pintype "unspecified"))
      (node (ref "U10") (pin "40") (pinfunction "IO3_3_40") (pintype "unspecified"))
    )
    (net (code "79") (name "2_IO_3_4") (class "Default")
      (node (ref "SW73") (pin "SW1") (pinfunction "SW1_SW1") (pintype "unspecified"))
      (node (ref "U10") (pin "41") (pinfunction "IO3_4_41") (pintype "unspecified"))
    )
    (net (code "80") (name "2_IO_3_5") (class "Default")
      (node (ref "SW76") (pin "SW1") (pinfunction "SW1_SW1") (pintype "unspecified"))
      (node (ref "U10") (pin "42") (pinfunction "IO3_5_42") (pintype "unspecified"))
    )
    (net (code "81") (name "2_IO_3_6") (class "Default")
      (node (ref "SW75") (pin "SW1") (pinfunction "SW1_SW1") (pintype "unspecified"))
      (node (ref "U10") (pin "43") (pinfunction "IO3_6_43") (pintype "unspecified"))
    )
    (net (code "82") (name "2_IO_3_7") (class "Default")
      (node (ref "SW82") (pin "SW1") (pinfunction "SW1_SW1") (pintype "unspecified"))
      (node (ref "U10") (pin "44") (pinfunction "IO3_7_44") (pintype "unspecified"))
    )
    (net (code "83") (name "2_IO_4_0") (class "Default")
      (node (ref "SW81") (pin "SW1") (pinfunction "SW1_SW1") (pintype "unspecified"))
      (node (ref "U10") (pin "45") (pinfunction "IO4_0_45") (pintype "unspecified"))
    )
    (net (code "84") (name "2_IO_4_1") (class "Default")
      (node (ref "SW80") (pin "SW1") (pinfunction "SW1_SW1") (pintype "unspecified"))
      (node (ref "U10") (pin "47") (pinfunction "IO4_1_47") (pintype "unspecified"))
    )
    (net (code "85") (name "2_IO_4_2") (class "Default")
      (node (ref "SW78") (pin "SW1") (pinfunction "SW1_SW1") (pintype "unspecified"))
      (node (ref "U10") (pin "48") (pinfunction "IO4_2_48") (pintype "unspecified"))
    )
    (net (code "86") (name "2_IO_4_3") (class "Default")
      (node (ref "SW83") (pin "SW1") (pinfunction "SW1_SW1") (pintype "unspecified"))
      (node (ref "U10") (pin "49") (pinfunction "IO4_3_49") (pintype "unspecified"))
    )
    (net (code "87") (name "2_IO_4_4") (class "Default")
      (node (ref "SW84") (pin "SW1") (pinfunction "SW1_SW1") (pintype "unspecified"))
      (node (ref "U10") (pin "50") (pinfunction "IO4_4_50") (pintype "unspecified"))
    )
    (net (code "88") (name "2_IO_4_5") (class "Default")
      (node (ref "SW86") (pin "SW1") (pinfunction "SW1_SW1") (pintype "unspecified"))
      (node (ref "U10") (pin "52") (pinfunction "IO4_5_52") (pintype "unspecified"))
    )
    (net (code "89") (name "2_IO_4_6") (class "Default")
      (node (ref "SW85") (pin "SW1") (pinfunction "SW1_SW1") (pintype "unspecified"))
      (node (ref "U10") (pin "53") (pinfunction "IO4_6_53") (pintype "unspecified"))
    )
    (net (code "90") (name "2_IO_4_7") (class "Default")
      (node (ref "SW88") (pin "SW1") (pinfunction "SW1_SW1") (pintype "unspecified"))
      (node (ref "U10") (pin "54") (pinfunction "IO4_7_54") (pintype "unspecified"))
    )
    (net (code "91") (name "2_OE_PCA") (class "Default")
      (node (ref "R10") (pin "2") (pinfunction "2_2") (pintype "unspecified"))
      (node (ref "U10") (pin "30") (pinfunction "OE#_30") (pintype "unspecified"))
    )
    (net (code "92") (name "2_RESET_PCA") (class "Default")
      (node (ref "R9") (pin "2") (pinfunction "2_2") (pintype "unspecified"))
      (node (ref "U10") (pin "56") (pinfunction "RESET#_56") (pintype "unspecified"))
    )
    (net (code "93") (name "3V3_PCA") (class "Default")
      (node (ref "H1") (pin "5") (pinfunction "5_5") (pintype "unspecified"))
      (node (ref "Q1") (pin "1") (pinfunction "G_1") (pintype "unspecified"))
      (node (ref "R17") (pin "2") (pinfunction "2_2") (pintype "unspecified"))
      (node (ref "U3") (pin "12") (pinfunction "3V3_12") (pintype "unspecified"))
    )
    (net (code "94") (name "3_A0") (class "Default")
      (node (ref "U17") (pin "1") (pinfunction "1_1") (pintype "unspecified"))
      (node (ref "U18") (pin "1") (pinfunction "1_1") (pintype "unspecified"))
      (node (ref "U23") (pin "27") (pinfunction "A0_27") (pintype "unspecified"))
    )
    (net (code "95") (name "3_A1") (class "Default")
      (node (ref "U19") (pin "1") (pinfunction "1_1") (pintype "unspecified"))
      (node (ref "U20") (pin "1") (pinfunction "1_1") (pintype "unspecified"))
      (node (ref "U23") (pin "28") (pinfunction "A1_28") (pintype "unspecified"))
    )
    (net (code "96") (name "3_A2") (class "Default")
      (node (ref "U21") (pin "1") (pinfunction "1_1") (pintype "unspecified"))
      (node (ref "U22") (pin "1") (pinfunction "1_1") (pintype "unspecified"))
      (node (ref "U23") (pin "29") (pinfunction "A2_29") (pintype "unspecified"))
    )
    (net (code "97") (name "3_INT_PCA") (class "Default")
      (node (ref "R13") (pin "2") (pinfunction "2_2") (pintype "unspecified"))
      (node (ref "U23") (pin "55") (pinfunction "INT#_55") (pintype "unspecified"))
    )
    (net (code "98") (name "3_IO_0_0") (class "Default")
      (node (ref "SW87") (pin "SW1") (pinfunction "SW1_SW1") (pintype "unspecified"))
      (node (ref "U23") (pin "3") (pinfunction "IO0_0_3") (pintype "unspecified"))
    )
    (net (code "99") (name "3_IO_0_1") (class "Default")
      (node (ref "SW94") (pin "SW1") (pinfunction "SW1_SW1") (pintype "unspecified"))
      (node (ref "U23") (pin "4") (pinfunction "IO0_1_4") (pintype "unspecified"))
    )
    (net (code "100") (name "3_IO_0_2") (class "Default")
      (node (ref "SW93") (pin "SW1") (pinfunction "SW1_SW1") (pintype "unspecified"))
      (node (ref "U23") (pin "5") (pinfunction "IO0_2_5") (pintype "unspecified"))
    )
    (net (code "101") (name "3_IO_0_3") (class "Default")
      (node (ref "SW91") (pin "SW1") (pinfunction "SW1_SW1") (pintype "unspecified"))
      (node (ref "U23") (pin "7") (pinfunction "IO0_3_7") (pintype "unspecified"))
    )
    (net (code "102") (name "3_IO_0_4") (class "Default")
      (node (ref "SW92") (pin "SW1") (pinfunction "SW1_SW1") (pintype "unspecified"))
      (node (ref "U23") (pin "8") (pinfunction "IO0_4_8") (pintype "unspecified"))
    )
    (net (code "103") (name "3_IO_0_5") (class "Default")
      (node (ref "SW89") (pin "SW1") (pinfunction "SW1_SW1") (pintype "unspecified"))
      (node (ref "U23") (pin "9") (pinfunction "IO0_5_9") (pintype "unspecified"))
    )
    (net (code "104") (name "3_IO_0_6") (class "Default")
      (node (ref "SW95") (pin "SW1") (pinfunction "SW1_SW1") (pintype "unspecified"))
      (node (ref "U23") (pin "10") (pinfunction "IO0_6_10") (pintype "unspecified"))
    )
    (net (code "105") (name "3_IO_0_7") (class "Default")
      (node (ref "SW96") (pin "SW1") (pinfunction "SW1_SW1") (pintype "unspecified"))
      (node (ref "U23") (pin "12") (pinfunction "IO0_7_12") (pintype "unspecified"))
    )
    (net (code "106") (name "3_IO_1_0") (class "Default")
      (node (ref "SW98") (pin "SW1") (pinfunction "SW1_SW1") (pintype "unspecified"))
      (node (ref "U23") (pin "13") (pinfunction "IO1_0_13") (pintype "unspecified"))
    )
    (net (code "107") (name "3_IO_1_1") (class "Default")
      (node (ref "SW97") (pin "SW1") (pinfunction "SW1_SW1") (pintype "unspecified"))
      (node (ref "U23") (pin "14") (pinfunction "IO1_1_14") (pintype "unspecified"))
    )
    (net (code "108") (name "3_IO_1_2") (class "Default")
      (node (ref "SW100") (pin "SW1") (pinfunction "SW1_SW1") (pintype "unspecified"))
      (node (ref "U23") (pin "15") (pinfunction "IO1_2_15") (pintype "unspecified"))
    )
    (net (code "109") (name "3_IO_1_3") (class "Default")
      (node (ref "SW99") (pin "SW1") (pinfunction "SW1_SW1") (pintype "unspecified"))
      (node (ref "U23") (pin "16") (pinfunction "IO1_3_16") (pintype "unspecified"))
    )
    (net (code "110") (name "3_IO_1_4") (class "Default")
      (node (ref "SW104") (pin "SW1") (pinfunction "SW1_SW1") (pintype "unspecified"))
      (node (ref "U23") (pin "17") (pinfunction "IO1_4_17") (pintype "unspecified"))
    )
    (net (code "111") (name "3_IO_1_5") (class "Default")
      (node (ref "SW101") (pin "SW1") (pinfunction "SW1_SW1") (pintype "unspecified"))
      (node (ref "U23") (pin "19") (pinfunction "IO1_5_19") (pintype "unspecified"))
    )
    (net (code "112") (name "3_IO_1_6") (class "Default")
      (node (ref "SW102") (pin "SW1") (pinfunction "SW1_SW1") (pintype "unspecified"))
      (node (ref "U23") (pin "20") (pinfunction "IO1_6_20") (pintype "unspecified"))
    )
    (net (code "113") (name "3_IO_1_7") (class "Default")
      (node (ref "U23") (pin "21") (pinfunction "IO1_7_21") (pintype "unspecified"))
    )
    (net (code "114") (name "3_IO_2_0") (class "Default")
      (node (ref "U23") (pin "22") (pinfunction "IO2_0_22") (pintype "unspecified"))
    )
    (net (code "115") (name "3_IO_2_1") (class "Default")
      (node (ref "U23") (pin "24") (pinfunction "IO2_1_24") (pintype "unspecified"))
    )
    (net (code "116") (name "3_IO_2_2") (class "Default")
      (node (ref "U23") (pin "25") (pinfunction "IO2_2_25") (pintype "unspecified"))
    )
    (net (code "117") (name "3_IO_2_3") (class "Default")
      (node (ref "U23") (pin "26") (pinfunction "IO2_3_26") (pintype "unspecified"))
    )
    (net (code "118") (name "3_IO_2_4") (class "Default")
      (node (ref "U23") (pin "31") (pinfunction "IO2_4_31") (pintype "unspecified"))
    )
    (net (code "119") (name "3_IO_2_5") (class "Default")
      (node (ref "U23") (pin "32") (pinfunction "IO2_5_32") (pintype "unspecified"))
    )
    (net (code "120") (name "3_IO_2_6") (class "Default")
      (node (ref "U23") (pin "33") (pinfunction "IO2_6_33") (pintype "unspecified"))
    )
    (net (code "121") (name "3_IO_2_7") (class "Default")
      (node (ref "U23") (pin "35") (pinfunction "IO2_7_35") (pintype "unspecified"))
    )
    (net (code "122") (name "3_IO_3_0") (class "Default")
      (node (ref "U23") (pin "36") (pinfunction "IO3_0_36") (pintype "unspecified"))
    )
    (net (code "123") (name "3_IO_3_1") (class "Default")
      (node (ref "U23") (pin "37") (pinfunction "IO3_1_37") (pintype "unspecified"))
    )
    (net (code "124") (name "3_IO_3_2") (class "Default")
      (node (ref "U23") (pin "38") (pinfunction "IO3_2_38") (pintype "unspecified"))
    )
    (net (code "125") (name "3_IO_3_3") (class "Default")
      (node (ref "U23") (pin "40") (pinfunction "IO3_3_40") (pintype "unspecified"))
    )
    (net (code "126") (name "3_IO_3_4") (class "Default")
      (node (ref "U23") (pin "41") (pinfunction "IO3_4_41") (pintype "unspecified"))
    )
    (net (code "127") (name "3_IO_3_5") (class "Default")
      (node (ref "U23") (pin "42") (pinfunction "IO3_5_42") (pintype "unspecified"))
    )
    (net (code "128") (name "3_IO_3_6") (class "Default")
      (node (ref "U23") (pin "43") (pinfunction "IO3_6_43") (pintype "unspecified"))
    )
    (net (code "129") (name "3_IO_3_7") (class "Default")
      (node (ref "U23") (pin "44") (pinfunction "IO3_7_44") (pintype "unspecified"))
    )
    (net (code "130") (name "3_IO_4_0") (class "Default")
      (node (ref "U23") (pin "45") (pinfunction "IO4_0_45") (pintype "unspecified"))
    )
    (net (code "131") (name "3_IO_4_1") (class "Default")
      (node (ref "U23") (pin "47") (pinfunction "IO4_1_47") (pintype "unspecified"))
    )
    (net (code "132") (name "3_IO_4_2") (class "Default")
      (node (ref "U23") (pin "48") (pinfunction "IO4_2_48") (pintype "unspecified"))
    )
    (net (code "133") (name "3_IO_4_3") (class "Default")
      (node (ref "U23") (pin "49") (pinfunction "IO4_3_49") (pintype "unspecified"))
    )
    (net (code "134") (name "3_IO_4_4") (class "Default")
      (node (ref "U23") (pin "50") (pinfunction "IO4_4_50") (pintype "unspecified"))
    )
    (net (code "135") (name "3_IO_4_5") (class "Default")
      (node (ref "U23") (pin "52") (pinfunction "IO4_5_52") (pintype "unspecified"))
    )
    (net (code "136") (name "3_IO_4_6") (class "Default")
      (node (ref "U23") (pin "53") (pinfunction "IO4_6_53") (pintype "unspecified"))
    )
    (net (code "137") (name "3_IO_4_7") (class "Default")
      (node (ref "U23") (pin "54") (pinfunction "IO4_7_54") (pintype "unspecified"))
    )
    (net (code "138") (name "3_OE_PCA") (class "Default")
      (node (ref "R11") (pin "2") (pinfunction "2_2") (pintype "unspecified"))
      (node (ref "U23") (pin "30") (pinfunction "OE#_30") (pintype "unspecified"))
    )
    (net (code "139") (name "3_RESET_PCA") (class "Default")
      (node (ref "R12") (pin "2") (pinfunction "2_2") (pintype "unspecified"))
      (node (ref "U23") (pin "56") (pinfunction "RESET#_56") (pintype "unspecified"))
    )
    (net (code "140") (name "LED_IN") (class "Default")
      (node (ref "Q1") (pin "3") (pinfunction "D_3") (pintype "unspecified"))
      (node (ref "R16") (pin "1") (pinfunction "1_1") (pintype "unspecified"))
      (node (ref "SW0") (pin "DI") (pinfunction "DI_DI") (pintype "unspecified"))
    )
    (net (code "141") (name "LED_OUT") (class "Default")
      (node (ref "SW102") (pin "DO") (pinfunction "DO_DO") (pintype "unspecified"))
    )
    (net (code "142") (name "MCU_LED_OUT") (class "Default")
      (node (ref "H3") (pin "1") (pinfunction "1_1") (pintype "unspecified"))
      (node (ref "Q1") (pin "2") (pinfunction "S_2") (pintype "unspecified"))
      (node (ref "R17") (pin "1") (pinfunction "1_1") (pintype "unspecified"))
      (node (ref "U3") (pin "1") (pinfunction "P0.2_1") (pintype "unspecified"))
    )
    (net (code "143") (name "Net-(SW0-PadDO)") (class "Default")
      (node (ref "SW0") (pin "DO") (pinfunction "DO_DO") (pintype "unspecified"))
      (node (ref "SW1") (pin "DI") (pinfunction "DI_DI") (pintype "unspecified"))
    )
    (net (code "144") (name "Net-(SW1-PadDO)") (class "Default")
      (node (ref "SW1") (pin "DO") (pinfunction "DO_DO") (pintype "unspecified"))
      (node (ref "SW2") (pin "DI") (pinfunction "DI_DI") (pintype "unspecified"))
    )
    (net (code "145") (name "Net-(SW2-PadDO)") (class "Default")
      (node (ref "SW2") (pin "DO") (pinfunction "DO_DO") (pintype "unspecified"))
      (node (ref "SW3") (pin "DI") (pinfunction "DI_DI") (pintype "unspecified"))
    )
    (net (code "146") (name "Net-(SW3-PadDO)") (class "Default")
      (node (ref "SW3") (pin "DO") (pinfunction "DO_DO") (pintype "unspecified"))
      (node (ref "SW4") (pin "DI") (pinfunction "DI_DI") (pintype "unspecified"))
    )
    (net (code "147") (name "Net-(SW4-PadDO)") (class "Default")
      (node (ref "SW4") (pin "DO") (pinfunction "DO_DO") (pintype "unspecified"))
      (node (ref "SW5") (pin "DI") (pinfunction "DI_DI") (pintype "unspecified"))
    )
    (net (code "148") (name "Net-(SW6-PadDI)") (class "Default")
      (node (ref "SW6") (pin "DI") (pinfunction "DI_DI") (pintype "unspecified"))
      (node (ref "SW9") (pin "DO") (pinfunction "DO_DO") (pintype "unspecified"))
    )
    (net (code "149") (name "Net-(SW6-PadDO)") (class "Default")
      (node (ref "SW6") (pin "DO") (pinfunction "DO_DO") (pintype "unspecified"))
      (node (ref "SW7") (pin "DI") (pinfunction "DI_DI") (pintype "unspecified"))
    )
    (net (code "150") (name "Net-(SW8-PadDO)") (class "Default")
      (node (ref "SW8") (pin "DO") (pinfunction "DO_DO") (pintype "unspecified"))
      (node (ref "SW9") (pin "DI") (pinfunction "DI_DI") (pintype "unspecified"))
    )
    (net (code "151") (name "Net-(SW10-PadDI)") (class "Default")
      (node (ref "SW10") (pin "DI") (pinfunction "DI_DI") (pintype "unspecified"))
      (node (ref "SW5") (pin "DO") (pinfunction "DO_DO") (pintype "unspecified"))
    )
    (net (code "152") (name "Net-(SW10-PadDO)") (class "Default")
      (node (ref "SW10") (pin "DO") (pinfunction "DO_DO") (pintype "unspecified"))
      (node (ref "SW8") (pin "DI") (pinfunction "DI_DI") (pintype "unspecified"))
    )
    (net (code "153") (name "Net-(SW11-PadDI)") (class "Default")
      (node (ref "SW11") (pin "DI") (pinfunction "DI_DI") (pintype "unspecified"))
      (node (ref "SW16") (pin "DO") (pinfunction "DO_DO") (pintype "unspecified"))
    )
    (net (code "154") (name "Net-(SW11-PadDO)") (class "Default")
      (node (ref "SW11") (pin "DO") (pinfunction "DO_DO") (pintype "unspecified"))
      (node (ref "SW24") (pin "DI") (pinfunction "DI_DI") (pintype "unspecified"))
    )
    (net (code "155") (name "Net-(SW12-PadDI)") (class "Default")
      (node (ref "SW12") (pin "DI") (pinfunction "DI_DI") (pintype "unspecified"))
      (node (ref "SW19") (pin "DO") (pinfunction "DO_DO") (pintype "unspecified"))
    )
    (net (code "156") (name "Net-(SW12-PadDO)") (class "Default")
      (node (ref "SW12") (pin "DO") (pinfunction "DO_DO") (pintype "unspecified"))
      (node (ref "SW13") (pin "DI") (pinfunction "DI_DI") (pintype "unspecified"))
    )
    (net (code "157") (name "Net-(SW13-PadDO)") (class "Default")
      (node (ref "SW13") (pin "DO") (pinfunction "DO_DO") (pintype "unspecified"))
      (node (ref "SW15") (pin "DI") (pinfunction "DI_DI") (pintype "unspecified"))
    )
    (net (code "158") (name "Net-(SW14-PadDI)") (class "Default")
      (node (ref "SW14") (pin "DI") (pinfunction "DI_DI") (pintype "unspecified"))
      (node (ref "SW15") (pin "DO") (pinfunction "DO_DO") (pintype "unspecified"))
    )
    (net (code "159") (name "Net-(SW14-PadDO)") (class "Default")
      (node (ref "SW14") (pin "DO") (pinfunction "DO_DO") (pintype "unspecified"))
      (node (ref "SW17") (pin "DI") (pinfunction "DI_DI") (pintype "unspecified"))
    )
    (net (code "160") (name "Net-(SW16-PadDI)") (class "Default")
      (node (ref "SW16") (pin "DI") (pinfunction "DI_DI") (pintype "unspecified"))
      (node (ref "SW17") (pin "DO") (pinfunction "DO_DO") (pintype "unspecified"))
    )
    (net (code "161") (name "Net-(SW18-PadDI)") (class "Default")
      (node (ref "SW18") (pin "DI") (pinfunction "DI_DI") (pintype "unspecified"))
      (node (ref "SW21") (pin "DO") (pinfunction "DO_DO") (pintype "unspecified"))
    )
    (net (code "162") (name "Net-(SW18-PadDO)") (class "Default")
      (node (ref "SW18") (pin "DO") (pinfunction "DO_DO") (pintype "unspecified"))
      (node (ref "SW19") (pin "DI") (pinfunction "DI_DI") (pintype "unspecified"))
    )
    (net (code "163") (name "Net-(SW20-PadDI)") (class "Default")
      (node (ref "SW20") (pin "DI") (pinfunction "DI_DI") (pintype "unspecified"))
      (node (ref "SW22") (pin "DO") (pinfunction "DO_DO") (pintype "unspecified"))
    )
    (net (code "164") (name "Net-(SW20-PadDO)") (class "Default")
      (node (ref "SW20") (pin "DO") (pinfunction "DO_DO") (pintype "unspecified"))
      (node (ref "SW21") (pin "DI") (pinfunction "DI_DI") (pintype "unspecified"))
    )
    (net (code "165") (name "Net-(SW22-PadDI)") (class "Default")
      (node (ref "SW22") (pin "DI") (pinfunction "DI_DI") (pintype "unspecified"))
      (node (ref "SW23") (pin "DO") (pinfunction "DO_DO") (pintype "unspecified"))
    )
    (net (code "166") (name "Net-(SW23-PadDI)") (class "Default")
      (node (ref "SW23") (pin "DI") (pinfunction "DI_DI") (pintype "unspecified"))
      (node (ref "SW7") (pin "DO") (pinfunction "DO_DO") (pintype "unspecified"))
    )
    (net (code "167") (name "Net-(SW24-PadDO)") (class "Default")
      (node (ref "SW24") (pin "DO") (pinfunction "DO_DO") (pintype "unspecified"))
      (node (ref "SW26") (pin "DI") (pinfunction "DI_DI") (pintype "unspecified"))
    )
    (net (code "168") (name "Net-(SW25-PadDI)") (class "Default")
      (node (ref "SW25") (pin "DI") (pinfunction "DI_DI") (pintype "unspecified"))
      (node (ref "SW26") (pin "DO") (pinfunction "DO_DO") (pintype "unspecified"))
    )
    (net (code "169") (name "Net-(SW25-PadDO)") (class "Default")
      (node (ref "SW25") (pin "DO") (pinfunction "DO_DO") (pintype "unspecified"))
      (node (ref "SW28") (pin "DI") (pinfunction "DI_DI") (pintype "unspecified"))
    )
    (net (code "170") (name "Net-(SW28-PadDO)") (class "Default")
      (node (ref "SW28") (pin "DO") (pinfunction "DO_DO") (pintype "unspecified"))
      (node (ref "SW34") (pin "DI") (pinfunction "DI_DI") (pintype "unspecified"))
    )
    (net (code "171") (name "Net-(SW29-PadDI)") (class "Default")
      (node (ref "SW29") (pin "DI") (pinfunction "DI_DI") (pintype "unspecified"))
      (node (ref "SW32") (pin "DO") (pinfunction "DO_DO") (pintype "unspecified"))
    )
    (net (code "172") (name "Net-(SW29-PadDO)") (class "Default")
      (node (ref "SW29") (pin "DO") (pinfunction "DO_DO") (pintype "unspecified"))
      (node (ref "SW35") (pin "DI") (pinfunction "DI_DI") (pintype "unspecified"))
    )
    (net (code "173") (name "Net-(SW31-PadDI)") (class "Default")
      (node (ref "SW31") (pin "DI") (pinfunction "DI_DI") (pintype "unspecified"))
      (node (ref "SW33") (pin "DO") (pinfunction "DO_DO") (pintype "unspecified"))
    )
    (net (code "174") (name "Net-(SW31-PadDO)") (class "Default")
      (node (ref "SW31") (pin "DO") (pinfunction "DO_DO") (pintype "unspecified"))
      (node (ref "SW32") (pin "DI") (pinfunction "DI_DI") (pintype "unspecified"))
    )
    (net (code "175") (name "Net-(SW33-PadDI)") (class "Default")
      (node (ref "SW33") (pin "DI") (pinfunction "DI_DI") (pintype "unspecified"))
      (node (ref "SW34") (pin "DO") (pinfunction "DO_DO") (pintype "unspecified"))
    )
    (net (code "176") (name "Net-(SW35-PadDO)") (class "Default")
      (node (ref "SW35") (pin "DO") (pinfunction "DO_DO") (pintype "unspecified"))
      (node (ref "SW36") (pin "DI") (pinfunction "DI_DI") (pintype "unspecified"))
    )
    (net (code "177") (name "Net-(SW36-PadDO)") (class "Default")
      (node (ref "SW36") (pin "DO") (pinfunction "DO_DO") (pintype "unspecified"))
      (node (ref "SW38") (pin "DI") (pinfunction "DI_DI") (pintype "unspecified"))
    )
    (net (code "178") (name "Net-(SW37-PadDI)") (class "Default")
      (node (ref "SW37") (pin "DI") (pinfunction "DI_DI") (pintype "unspecified"))
      (node (ref "SW38") (pin "DO") (pinfunction "DO_DO") (pintype "unspecified"))
    )
    (net (code "179") (name "Net-(SW37-PadDO)") (class "Default")
      (node (ref "SW37") (pin "DO") (pinfunction "DO_DO") (pintype "unspecified"))
      (node (ref "SW40") (pin "DI") (pinfunction "DI_DI") (pintype "unspecified"))
    )
    (net (code "180") (name "Net-(SW40-PadDO)") (class "Default")
      (node (ref "SW40") (pin "DO") (pinfunction "DO_DO") (pintype "unspecified"))
      (node (ref "SW46") (pin "DI") (pinfunction "DI_DI") (pintype "unspecified"))
    )
    (net (code "181") (name "Net-(SW41-PadDI)") (class "Default")
      (node (ref "SW41") (pin "DI") (pinfunction "DI_DI") (pintype "unspecified"))
      (node (ref "SW44") (pin "DO") (pinfunction "DO_DO") (pintype "unspecified"))
    )
    (net (code "182") (name "Net-(SW41-PadDO)") (class "Default")
      (node (ref "SW41") (pin "DO") (pinfunction "DO_DO") (pintype "unspecified"))
      (node (ref "SW42") (pin "DI") (pinfunction "DI_DI") (pintype "unspecified"))
    )
    (net (code "183") (name "Net-(SW42-PadDO)") (class "Default")
      (node (ref "SW42") (pin "DO") (pinfunction "DO_DO") (pintype "unspecified"))
      (node (ref "SW47") (pin "DI") (pinfunction "DI_DI") (pintype "unspecified"))
    )
    (net (code "184") (name "Net-(SW43-PadDI)") (class "Default")
      (node (ref "SW43") (pin "DI") (pinfunction "DI_DI") (pintype "unspecified"))
      (node (ref "SW45") (pin "DO") (pinfunction "DO_DO") (pintype "unspecified"))
    )
    (net (code "185") (name "Net-(SW43-PadDO)") (class "Default")
      (node (ref "SW43") (pin "DO") (pinfunction "DO_DO") (pintype "unspecified"))
      (node (ref "SW44") (pin "DI") (pinfunction "DI_DI") (pintype "unspecified"))
    )
    (net (code "186") (name "Net-(SW45-PadDI)") (class "Default")
      (node (ref "SW45") (pin "DI") (pinfunction "DI_DI") (pintype "unspecified"))
      (node (ref "SW46") (pin "DO") (pinfunction "DO_DO") (pintype "unspecified"))
    )
    (net (code "187") (name "Net-(SW47-PadDO)") (class "Default")
      (node (ref "SW47") (pin "DO") (pinfunction "DO_DO") (pintype "unspecified"))
      (node (ref "SW48") (pin "DI") (pinfunction "DI_DI") (pintype "unspecified"))
    )
    (net (code "188") (name "Net-(SW48-PadDO)") (class "Default")
      (node (ref "SW48") (pin "DO") (pinfunction "DO_DO") (pintype "unspecified"))
      (node (ref "SW50") (pin "DI") (pinfunction "DI_DI") (pintype "unspecified"))
    )
    (net (code "189") (name "Net-(SW49-PadDI)") (class "Default")
      (node (ref "SW49") (pin "DI") (pinfunction "DI_DI") (pintype "unspecified"))
      (node (ref "SW50") (pin "DO") (pinfunction "DO_DO") (pintype "unspecified"))
    )
    (net (code "190") (name "Net-(SW49-PadDO)") (class "Default")
      (node (ref "SW49") (pin "DO") (pinfunction "DO_DO") (pintype "unspecified"))
      (node (ref "SW52") (pin "DI") (pinfunction "DI_DI") (pintype "unspecified"))
    )
    (net (code "191") (name "Net-(SW52-PadDO)") (class "Default")
      (node (ref "SW52") (pin "DO") (pinfunction "DO_DO") (pintype "unspecified"))
      (node (ref "SW58") (pin "DI") (pinfunction "DI_DI") (pintype "unspecified"))
    )
    (net (code "192") (name "Net-(SW53-PadDI)") (class "Default")
      (node (ref "SW53") (pin "DI") (pinfunction "DI_DI") (pintype "unspecified"))
      (node (ref "SW56") (pin "DO") (pinfunction "DO_DO") (pintype "unspecified"))
    )
    (net (code "193") (name "Net-(SW53-PadDO)") (class "Default")
      (node (ref "SW53") (pin "DO") (pinfunction "DO_DO") (pintype "unspecified"))
      (node (ref "SW59") (pin "DI") (pinfunction "DI_DI") (pintype "unspecified"))
    )
    (net (code "194") (name "Net-(SW55-PadDI)") (class "Default")
      (node (ref "SW55") (pin "DI") (pinfunction "DI_DI") (pintype "unspecified"))
      (node (ref "SW57") (pin "DO") (pinfunction "DO_DO") (pintype "unspecified"))
    )
    (net (code "195") (name "Net-(SW55-PadDO)") (class "Default")
      (node (ref "SW55") (pin "DO") (pinfunction "DO_DO") (pintype "unspecified"))
      (node (ref "SW56") (pin "DI") (pinfunction "DI_DI") (pintype "unspecified"))
    )
    (net (code "196") (name "Net-(SW57-PadDI)") (class "Default")
      (node (ref "SW57") (pin "DI") (pinfunction "DI_DI") (pintype "unspecified"))
      (node (ref "SW58") (pin "DO") (pinfunction "DO_DO") (pintype "unspecified"))
    )
    (net (code "197") (name "Net-(SW59-PadDO)") (class "Default")
      (node (ref "SW59") (pin "DO") (pinfunction "DO_DO") (pintype "unspecified"))
      (node (ref "SW60") (pin "DI") (pinfunction "DI_DI") (pintype "unspecified"))
    )
    (net (code "198") (name "Net-(SW60-PadDO)") (class "Default")
      (node (ref "SW60") (pin "DO") (pinfunction "DO_DO") (pintype "unspecified"))
      (node (ref "SW62") (pin "DI") (pinfunction "DI_DI") (pintype "unspecified"))
    )
    (net (code "199") (name "Net-(SW61-PadDI)") (class "Default")
      (node (ref "SW61") (pin "DI") (pinfunction "DI_DI") (pintype "unspecified"))
      (node (ref "SW62") (pin "DO") (pinfunction "DO_DO") (pintype "unspecified"))
    )
    (net (code "200") (name "Net-(SW61-PadDO)") (class "Default")
      (node (ref "SW61") (pin "DO") (pinfunction "DO_DO") (pintype "unspecified"))
      (node (ref "SW64") (pin "DI") (pinfunction "DI_DI") (pintype "unspecified"))
    )
    (net (code "201") (name "Net-(SW64-PadDO)") (class "Default")
      (node (ref "SW64") (pin "DO") (pinfunction "DO_DO") (pintype "unspecified"))
      (node (ref "SW70") (pin "DI") (pinfunction "DI_DI") (pintype "unspecified"))
    )
    (net (code "202") (name "Net-(SW65-PadDI)") (class "Default")
      (node (ref "SW65") (pin "DI") (pinfunction "DI_DI") (pintype "unspecified"))
      (node (ref "SW68") (pin "DO") (pinfunction "DO_DO") (pintype "unspecified"))
    )
    (net (code "203") (name "Net-(SW65-PadDO)") (class "Default")
      (node (ref "SW65") (pin "DO") (pinfunction "DO_DO") (pintype "unspecified"))
      (node (ref "SW66") (pin "DI") (pinfunction "DI_DI") (pintype "unspecified"))
    )
    (net (code "204") (name "Net-(SW66-PadDO)") (class "Default")
      (node (ref "SW66") (pin "DO") (pinfunction "DO_DO") (pintype "unspecified"))
      (node (ref "SW71") (pin "DI") (pinfunction "DI_DI") (pintype "unspecified"))
    )
    (net (code "205") (name "Net-(SW67-PadDI)") (class "Default")
      (node (ref "SW67") (pin "DI") (pinfunction "DI_DI") (pintype "unspecified"))
      (node (ref "SW69") (pin "DO") (pinfunction "DO_DO") (pintype "unspecified"))
    )
    (net (code "206") (name "Net-(SW67-PadDO)") (class "Default")
      (node (ref "SW67") (pin "DO") (pinfunction "DO_DO") (pintype "unspecified"))
      (node (ref "SW68") (pin "DI") (pinfunction "DI_DI") (pintype "unspecified"))
    )
    (net (code "207") (name "Net-(SW69-PadDI)") (class "Default")
      (node (ref "SW69") (pin "DI") (pinfunction "DI_DI") (pintype "unspecified"))
      (node (ref "SW70") (pin "DO") (pinfunction "DO_DO") (pintype "unspecified"))
    )
    (net (code "208") (name "Net-(SW71-PadDO)") (class "Default")
      (node (ref "SW71") (pin "DO") (pinfunction "DO_DO") (pintype "unspecified"))
      (node (ref "SW72") (pin "DI") (pinfunction "DI_DI") (pintype "unspecified"))
    )
    (net (code "209") (name "Net-(SW72-PadDO)") (class "Default")
      (node (ref "SW72") (pin "DO") (pinfunction "DO_DO") (pintype "unspecified"))
      (node (ref "SW74") (pin "DI") (pinfunction "DI_DI") (pintype "unspecified"))
    )
    (net (code "210") (name "Net-(SW73-PadDI)") (class "Default")
      (node (ref "SW73") (pin "DI") (pinfunction "DI_DI") (pintype "unspecified"))
      (node (ref "SW74") (pin "DO") (pinfunction "DO_DO") (pintype "unspecified"))
    )
    (net (code "211") (name "Net-(SW73-PadDO)") (class "Default")
      (node (ref "SW73") (pin "DO") (pinfunction "DO_DO") (pintype "unspecified"))
      (node (ref "SW76") (pin "DI") (pinfunction "DI_DI") (pintype "unspecified"))
    )
    (net (code "212") (name "Net-(SW75-PadDI)") (class "Default")
      (node (ref "SW75") (pin "DI") (pinfunction "DI_DI") (pintype "unspecified"))
      (node (ref "SW76") (pin "DO") (pinfunction "DO_DO") (pintype "unspecified"))
    )
    (net (code "213") (name "Net-(SW75-PadDO)") (class "Default")
      (node (ref "SW75") (pin "DO") (pinfunction "DO_DO") (pintype "unspecified"))
      (node (ref "SW82") (pin "DI") (pinfunction "DI_DI") (pintype "unspecified"))
    )
    (net (code "214") (name "Net-(SW78-PadDI)") (class "Default")
      (node (ref "SW78") (pin "DI") (pinfunction "DI_DI") (pintype "unspecified"))
      (node (ref "SW80") (pin "DO") (pinfunction "DO_DO") (pintype "unspecified"))
    )
    (net (code "215") (name "Net-(SW78-PadDO)") (class "Default")
      (node (ref "SW78") (pin "DO") (pinfunction "DO_DO") (pintype "unspecified"))
      (node (ref "SW83") (pin "DI") (pinfunction "DI_DI") (pintype "unspecified"))
    )
    (net (code "216") (name "Net-(SW80-PadDI)") (class "Default")
      (node (ref "SW80") (pin "DI") (pinfunction "DI_DI") (pintype "unspecified"))
      (node (ref "SW81") (pin "DO") (pinfunction "DO_DO") (pintype "unspecified"))
    )
    (net (code "217") (name "Net-(SW81-PadDI)") (class "Default")
      (node (ref "SW81") (pin "DI") (pinfunction "DI_DI") (pintype "unspecified"))
      (node (ref "SW82") (pin "DO") (pinfunction "DO_DO") (pintype "unspecified"))
    )
    (net (code "218") (name "Net-(SW83-PadDO)") (class "Default")
      (node (ref "SW83") (pin "DO") (pinfunction "DO_DO") (pintype "unspecified"))
      (node (ref "SW84") (pin "DI") (pinfunction "DI_DI") (pintype "unspecified"))
    )
    (net (code "219") (name "Net-(SW84-PadDO)") (class "Default")
      (node (ref "SW84") (pin "DO") (pinfunction "DO_DO") (pintype "unspecified"))
      (node (ref "SW86") (pin "DI") (pinfunction "DI_DI") (pintype "unspecified"))
    )
    (net (code "220") (name "Net-(SW85-PadDI)") (class "Default")
      (node (ref "SW85") (pin "DI") (pinfunction "DI_DI") (pintype "unspecified"))
      (node (ref "SW86") (pin "DO") (pinfunction "DO_DO") (pintype "unspecified"))
    )
    (net (code "221") (name "Net-(SW85-PadDO)") (class "Default")
      (node (ref "SW85") (pin "DO") (pinfunction "DO_DO") (pintype "unspecified"))
      (node (ref "SW88") (pin "DI") (pinfunction "DI_DI") (pintype "unspecified"))
    )
    (net (code "222") (name "Net-(SW87-PadDI)") (class "Default")
      (node (ref "SW87") (pin "DI") (pinfunction "DI_DI") (pintype "unspecified"))
      (node (ref "SW88") (pin "DO") (pinfunction "DO_DO") (pintype "unspecified"))
    )
    (net (code "223") (name "Net-(SW87-PadDO)") (class "Default")
      (node (ref "SW87") (pin "DO") (pinfunction "DO_DO") (pintype "unspecified"))
      (node (ref "SW94") (pin "DI") (pinfunction "DI_DI") (pintype "unspecified"))
    )
    (net (code "224") (name "Net-(SW89-PadDI)") (class "Default")
      (node (ref "SW89") (pin "DI") (pinfunction "DI_DI") (pintype "unspecified"))
      (node (ref "SW92") (pin "DO") (pinfunction "DO_DO") (pintype "unspecified"))
    )
    (net (code "225") (name "Net-(SW89-PadDO)") (class "Default")
      (node (ref "SW89") (pin "DO") (pinfunction "DO_DO") (pintype "unspecified"))
      (node (ref "SW95") (pin "DI") (pinfunction "DI_DI") (pintype "unspecified"))
    )
    (net (code "226") (name "Net-(SW91-PadDI)") (class "Default")
      (node (ref "SW91") (pin "DI") (pinfunction "DI_DI") (pintype "unspecified"))
      (node (ref "SW93") (pin "DO") (pinfunction "DO_DO") (pintype "unspecified"))
    )
    (net (code "227") (name "Net-(SW91-PadDO)") (class "Default")
      (node (ref "SW91") (pin "DO") (pinfunction "DO_DO") (pintype "unspecified"))
      (node (ref "SW92") (pin "DI") (pinfunction "DI_DI") (pintype "unspecified"))
    )
    (net (code "228") (name "Net-(SW93-PadDI)") (class "Default")
      (node (ref "SW93") (pin "DI") (pinfunction "DI_DI") (pintype "unspecified"))
      (node (ref "SW94") (pin "DO") (pinfunction "DO_DO") (pintype "unspecified"))
    )
    (net (code "229") (name "Net-(SW95-PadDO)") (class "Default")
      (node (ref "SW95") (pin "DO") (pinfunction "DO_DO") (pintype "unspecified"))
      (node (ref "SW96") (pin "DI") (pinfunction "DI_DI") (pintype "unspecified"))
    )
    (net (code "230") (name "Net-(SW96-PadDO)") (class "Default")
      (node (ref "SW96") (pin "DO") (pinfunction "DO_DO") (pintype "unspecified"))
      (node (ref "SW98") (pin "DI") (pinfunction "DI_DI") (pintype "unspecified"))
    )
    (net (code "231") (name "Net-(SW97-PadDI)") (class "Default")
      (node (ref "SW97") (pin "DI") (pinfunction "DI_DI") (pintype "unspecified"))
      (node (ref "SW98") (pin "DO") (pinfunction "DO_DO") (pintype "unspecified"))
    )
    (net (code "232") (name "Net-(SW100-PadDI)") (class "Default")
      (node (ref "SW100") (pin "DI") (pinfunction "DI_DI") (pintype "unspecified"))
      (node (ref "SW97") (pin "DO") (pinfunction "DO_DO") (pintype "unspecified"))
    )
    (net (code "233") (name "Net-(SW100-PadDO)") (class "Default")
      (node (ref "SW100") (pin "DO") (pinfunction "DO_DO") (pintype "unspecified"))
      (node (ref "SW99") (pin "DI") (pinfunction "DI_DI") (pintype "unspecified"))
    )
    (net (code "234") (name "Net-(SW101-PadDI)") (class "Default")
      (node (ref "SW101") (pin "DI") (pinfunction "DI_DI") (pintype "unspecified"))
      (node (ref "SW104") (pin "DO") (pinfunction "DO_DO") (pintype "unspecified"))
    )
    (net (code "235") (name "Net-(SW101-PadDO)") (class "Default")
      (node (ref "SW101") (pin "DO") (pinfunction "DO_DO") (pintype "unspecified"))
      (node (ref "SW102") (pin "DI") (pinfunction "DI_DI") (pintype "unspecified"))
    )
    (net (code "236") (name "Net-(SW104-PadDI)") (class "Default")
      (node (ref "SW104") (pin "DI") (pinfunction "DI_DI") (pintype "unspecified"))
      (node (ref "SW99") (pin "DO") (pinfunction "DO_DO") (pintype "unspecified"))
    )
    (net (code "237") (name "Net-(U3-P0.28)") (class "Default")
      (node (ref "H3") (pin "3") (pinfunction "3_3") (pintype "unspecified"))
      (node (ref "U3") (pin "3") (pinfunction "P0.28_3") (pintype "unspecified"))
    )
    (net (code "238") (name "Net-(U3-P0.29)") (class "Default")
      (node (ref "H3") (pin "4") (pinfunction "4_4") (pintype "unspecified"))
      (node (ref "U3") (pin "4") (pinfunction "P0.29_4") (pintype "unspecified"))
    )
    (net (code "239") (name "Net-(U3-P1.11)") (class "Default")
      (node (ref "H3") (pin "7") (pinfunction "7_7") (pintype "unspecified"))
      (node (ref "U3") (pin "7") (pinfunction "P1.11_7") (pintype "unspecified"))
    )
    (net (code "240") (name "Net-(U3-P1.12)") (class "Default")
      (node (ref "H1") (pin "1") (pinfunction "1_1") (pintype "unspecified"))
      (node (ref "U3") (pin "8") (pinfunction "P1.12_8") (pintype "unspecified"))
    )
    (net (code "241") (name "Net-(U3-P1.13)") (class "Default")
      (node (ref "H1") (pin "2") (pinfunction "2_2") (pintype "unspecified"))
      (node (ref "U3") (pin "9") (pinfunction "P1.13_9") (pintype "unspecified"))
    )
    (net (code "242") (name "Net-(U3-P1.14)") (class "Default")
      (node (ref "H1") (pin "3") (pinfunction "3_3") (pintype "unspecified"))
      (node (ref "U3") (pin "10") (pinfunction "P1.14_10") (pintype "unspecified"))
    )
    (net (code "243") (name "Net-(U3-P1.15)") (class "Default")
      (node (ref "H1") (pin "4") (pinfunction "4_4") (pintype "unspecified"))
      (node (ref "U3") (pin "11") (pinfunction "P1.15_11") (pintype "unspecified"))
    )
    (net (code "244") (name "POT_OUT") (class "Default")
      (node (ref "H3") (pin "2") (pinfunction "2_2") (pintype "unspecified"))
      (node (ref "H9") (pin "2") (pinfunction "2_2") (pintype "unspecified"))
      (node (ref "U3") (pin "2") (pinfunction "P0.3_2") (pintype "unspecified"))
    )
    (net (code "245") (name "SCL_PCA") (class "Default")
      (node (ref "H3") (pin "6") (pinfunction "6_6") (pintype "unspecified"))
      (node (ref "R15") (pin "2") (pinfunction "2_2") (pintype "unspecified"))
      (node (ref "R2") (pin "2") (pinfunction "2_2") (pintype "unspecified"))
      (node (ref "R6") (pin "2") (pinfunction "2_2") (pintype "unspecified"))
      (node (ref "U1") (pin "2") (pinfunction "SCL_2") (pintype "unspecified"))
      (node (ref "U10") (pin "2") (pinfunction "SCL_2") (pintype "unspecified"))
      (node (ref "U23") (pin "2") (pinfunction "SCL_2") (pintype "unspecified"))
      (node (ref "U3") (pin "6") (pinfunction "P0.5_6") (pintype "unspecified"))
    )
    (net (code "246") (name "SDA_PCA") (class "Default")
      (node (ref "H3") (pin "5") (pinfunction "5_5") (pintype "unspecified"))
      (node (ref "R1") (pin "2") (pinfunction "2_2") (pintype "unspecified"))
      (node (ref "R14") (pin "2") (pinfunction "2_2") (pintype "unspecified"))
      (node (ref "R7") (pin "2") (pinfunction "2_2") (pintype "unspecified"))
      (node (ref "U1") (pin "1") (pinfunction "SDA_1") (pintype "unspecified"))
      (node (ref "U10") (pin "1") (pinfunction "SDA_1") (pintype "unspecified"))
      (node (ref "U23") (pin "1") (pinfunction "SDA_1") (pintype "unspecified"))
      (node (ref "U3") (pin "5") (pinfunction "P0.4_5") (pintype "unspecified"))
    )
    (net (code "247") (name "VDD_PCA") (class "Default")
      (node (ref "C1") (pin "1") (pinfunction "1_1") (pintype "unspecified"))
      (node (ref "C2") (pin "1") (pinfunction "1_1") (pintype "unspecified"))
      (node (ref "C3") (pin "1") (pinfunction "1_1") (pintype "unspecified"))
      (node (ref "C4") (pin "1") (pinfunction "1_1") (pintype "unspecified"))
      (node (ref "C5") (pin "1") (pinfunction "1_1") (pintype "unspecified"))
      (node (ref "C6") (pin "1") (pinfunction "1_1") (pintype "unspecified"))
      (node (ref "H1") (pin "7") (pinfunction "7_7") (pintype "unspecified"))
      (node (ref "H9") (pin "1") (pinfunction "1_1") (pintype "unspecified"))
      (node (ref "R1") (pin "1") (pinfunction "1_1") (pintype "unspecified"))
      (node (ref "R10") (pin "1") (pinfunction "1_1") (pintype "unspecified"))
      (node (ref "R11") (pin "1") (pinfunction "1_1") (pintype "unspecified"))
      (node (ref "R12") (pin "1") (pinfunction "1_1") (pintype "unspecified"))
      (node (ref "R13") (pin "1") (pinfunction "1_1") (pintype "unspecified"))
      (node (ref "R14") (pin "1") (pinfunction "1_1") (pintype "unspecified"))
      (node (ref "R15") (pin "1") (pinfunction "1_1") (pintype "unspecified"))
      (node (ref "R16") (pin "2") (pinfunction "2_2") (pintype "unspecified"))
      (node (ref "R2") (pin "1") (pinfunction "1_1") (pintype "unspecified"))
      (node (ref "R3") (pin "1") (pinfunction "1_1") (pintype "unspecified"))
      (node (ref "R4") (pin "1") (pinfunction "1_1") (pintype "unspecified"))
      (node (ref "R5") (pin "1") (pinfunction "1_1") (pintype "unspecified"))
      (node (ref "R6") (pin "1") (pinfunction "1_1") (pintype "unspecified"))
      (node (ref "R7") (pin "1") (pinfunction "1_1") (pintype "unspecified"))
      (node (ref "R8") (pin "1") (pinfunction "1_1") (pintype "unspecified"))
      (node (ref "R9") (pin "1") (pinfunction "1_1") (pintype "unspecified"))
      (node (ref "SW0") (pin "VCC") (pinfunction "VCC_VCC") (pintype "unspecified"))
      (node (ref "SW1") (pin "VCC") (pinfunction "VCC_VCC") (pintype "unspecified"))
      (node (ref "SW10") (pin "VCC") (pinfunction "VCC_VCC") (pintype "unspecified"))
      (node (ref "SW100") (pin "VCC") (pinfunction "VCC_VCC") (pintype "unspecified"))
      (node (ref "SW101") (pin "VCC") (pinfunction "VCC_VCC") (pintype "unspecified"))
      (node (ref "SW102") (pin "VCC") (pinfunction "VCC_VCC") (pintype "unspecified"))
      (node (ref "SW104") (pin "VCC") (pinfunction "VCC_VCC") (pintype "unspecified"))
      (node (ref "SW11") (pin "VCC") (pinfunction "VCC_VCC") (pintype "unspecified"))
      (node (ref "SW12") (pin "VCC") (pinfunction "VCC_VCC") (pintype "unspecified"))
      (node (ref "SW13") (pin "VCC") (pinfunction "VCC_VCC") (pintype "unspecified"))
      (node (ref "SW14") (pin "VCC") (pinfunction "VCC_VCC") (pintype "unspecified"))
      (node (ref "SW15") (pin "VCC") (pinfunction "VCC_VCC") (pintype "unspecified"))
      (node (ref "SW16") (pin "VCC") (pinfunction "VCC_VCC") (pintype "unspecified"))
      (node (ref "SW17") (pin "VCC") (pinfunction "VCC_VCC") (pintype "unspecified"))
      (node (ref "SW18") (pin "VCC") (pinfunction "VCC_VCC") (pintype "unspecified"))
      (node (ref "SW19") (pin "VCC") (pinfunction "VCC_VCC") (pintype "unspecified"))
      (node (ref "SW2") (pin "VCC") (pinfunction "VCC_VCC") (pintype "unspecified"))
      (node (ref "SW20") (pin "VCC") (pinfunction "VCC_VCC") (pintype "unspecified"))
      (node (ref "SW21") (pin "VCC") (pinfunction "VCC_VCC") (pintype "unspecified"))
      (node (ref "SW22") (pin "VCC") (pinfunction "VCC_VCC") (pintype "unspecified"))
      (node (ref "SW23") (pin "VCC") (pinfunction "VCC_VCC") (pintype "unspecified"))
      (node (ref "SW24") (pin "VCC") (pinfunction "VCC_VCC") (pintype "unspecified"))
      (node (ref "SW25") (pin "VCC") (pinfunction "VCC_VCC") (pintype "unspecified"))
      (node (ref "SW26") (pin "VCC") (pinfunction "VCC_VCC") (pintype "unspecified"))
      (node (ref "SW28") (pin "VCC") (pinfunction "VCC_VCC") (pintype "unspecified"))
      (node (ref "SW29") (pin "VCC") (pinfunction "VCC_VCC") (pintype "unspecified"))
      (node (ref "SW3") (pin "VCC") (pinfunction "VCC_VCC") (pintype "unspecified"))
      (node (ref "SW31") (pin "VCC") (pinfunction "VCC_VCC") (pintype "unspecified"))
      (node (ref "SW32") (pin "VCC") (pinfunction "VCC_VCC") (pintype "unspecified"))
      (node (ref "SW33") (pin "VCC") (pinfunction "VCC_VCC") (pintype "unspecified"))
      (node (ref "SW34") (pin "VCC") (pinfunction "VCC_VCC") (pintype "unspecified"))
      (node (ref "SW35") (pin "VCC") (pinfunction "VCC_VCC") (pintype "unspecified"))
      (node (ref "SW36") (pin "VCC") (pinfunction "VCC_VCC") (pintype "unspecified"))
      (node (ref "SW37") (pin "VCC") (pinfunction "VCC_VCC") (pintype "unspecified"))
      (node (ref "SW38") (pin "VCC") (pinfunction "VCC_VCC") (pintype "unspecified"))
      (node (ref "SW4") (pin "VCC") (pinfunction "VCC_VCC") (pintype "unspecified"))
      (node (ref "SW40") (pin "VCC") (pinfunction "VCC_VCC") (pintype "unspecified"))
      (node (ref "SW41") (pin "VCC") (pinfunction "VCC_VCC") (pintype "unspecified"))
      (node (ref "SW42") (pin "VCC") (pinfunction "VCC_VCC") (pintype "unspecified"))
      (node (ref "SW43") (pin "VCC") (pinfunction "VCC_VCC") (pintype "unspecified"))
      (node (ref "SW44") (pin "VCC") (pinfunction "VCC_VCC") (pintype "unspecified"))
      (node (ref "SW45") (pin "VCC") (pinfunction "VCC_VCC") (pintype "unspecified"))
      (node (ref "SW46") (pin "VCC") (pinfunction "VCC_VCC") (pintype "unspecified"))
      (node (ref "SW47") (pin "VCC") (pinfunction "VCC_VCC") (pintype "unspecified"))
      (node (ref "SW48") (pin "VCC") (pinfunction "VCC_VCC") (pintype "unspecified"))
      (node (ref "SW49") (pin "VCC") (pinfunction "VCC_VCC") (pintype "unspecified"))
      (node (ref "SW5") (pin "VCC") (pinfunction "VCC_VCC") (pintype "unspecified"))
      (node (ref "SW50") (pin "VCC") (pinfunction "VCC_VCC") (pintype "unspecified"))
      (node (ref "SW52") (pin "VCC") (pinfunction "VCC_VCC") (pintype "unspecified"))
      (node (ref "SW53") (pin "VCC") (pinfunction "VCC_VCC") (pintype "unspecified"))
      (node (ref "SW55") (pin "VCC") (pinfunction "VCC_VCC") (pintype "unspecified"))
      (node (ref "SW56") (pin "VCC") (pinfunction "VCC_VCC") (pintype "unspecified"))
      (node (ref "SW57") (pin "VCC") (pinfunction "VCC_VCC") (pintype "unspecified"))
      (node (ref "SW58") (pin "VCC") (pinfunction "VCC_VCC") (pintype "unspecified"))
      (node (ref "SW59") (pin "VCC") (pinfunction "VCC_VCC") (pintype "unspecified"))
      (node (ref "SW6") (pin "VCC") (pinfunction "VCC_VCC") (pintype "unspecified"))
      (node (ref "SW60") (pin "VCC") (pinfunction "VCC_VCC") (pintype "unspecified"))
      (node (ref "SW61") (pin "VCC") (pinfunction "VCC_VCC") (pintype "unspecified"))
      (node (ref "SW62") (pin "VCC") (pinfunction "VCC_VCC") (pintype "unspecified"))
      (node (ref "SW64") (pin "VCC") (pinfunction "VCC_VCC") (pintype "unspecified"))
      (node (ref "SW65") (pin "VCC") (pinfunction "VCC_VCC") (pintype "unspecified"))
      (node (ref "SW66") (pin "VCC") (pinfunction "VCC_VCC") (pintype "unspecified"))
      (node (ref "SW67") (pin "VCC") (pinfunction "VCC_VCC") (pintype "unspecified"))
      (node (ref "SW68") (pin "VCC") (pinfunction "VCC_VCC") (pintype "unspecified"))
      (node (ref "SW69") (pin "VCC") (pinfunction "VCC_VCC") (pintype "unspecified"))
      (node (ref "SW7") (pin "VCC") (pinfunction "VCC_VCC") (pintype "unspecified"))
      (node (ref "SW70") (pin "VCC") (pinfunction "VCC_VCC") (pintype "unspecified"))
      (node (ref "SW71") (pin "VCC") (pinfunction "VCC_VCC") (pintype "unspecified"))
      (node (ref "SW72") (pin "VCC") (pinfunction "VCC_VCC") (pintype "unspecified"))
      (node (ref "SW73") (pin "VCC") (pinfunction "VCC_VCC") (pintype "unspecified"))
      (node (ref "SW74") (pin "VCC") (pinfunction "VCC_VCC") (pintype "unspecified"))
      (node (ref "SW75") (pin "VCC") (pinfunction "VCC_VCC") (pintype "unspecified"))
      (node (ref "SW76") (pin "VCC") (pinfunction "VCC_VCC") (pintype "unspecified"))
      (node (ref "SW78") (pin "VCC") (pinfunction "VCC_VCC") (pintype "unspecified"))
      (node (ref "SW8") (pin "VCC") (pinfunction "VCC_VCC") (pintype "unspecified"))
      (node (ref "SW80") (pin "VCC") (pinfunction "VCC_VCC") (pintype "unspecified"))
      (node (ref "SW81") (pin "VCC") (pinfunction "VCC_VCC") (pintype "unspecified"))
      (node (ref "SW82") (pin "VCC") (pinfunction "VCC_VCC") (pintype "unspecified"))
      (node (ref "SW83") (pin "VCC") (pinfunction "VCC_VCC") (pintype "unspecified"))
      (node (ref "SW84") (pin "VCC") (pinfunction "VCC_VCC") (pintype "unspecified"))
      (node (ref "SW85") (pin "VCC") (pinfunction "VCC_VCC") (pintype "unspecified"))
      (node (ref "SW86") (pin "VCC") (pinfunction "VCC_VCC") (pintype "unspecified"))
      (node (ref "SW87") (pin "VCC") (pinfunction "VCC_VCC") (pintype "unspecified"))
      (node (ref "SW88") (pin "VCC") (pinfunction "VCC_VCC") (pintype "unspecified"))
      (node (ref "SW89") (pin "VCC") (pinfunction "VCC_VCC") (pintype "unspecified"))
      (node (ref "SW9") (pin "VCC") (pinfunction "VCC_VCC") (pintype "unspecified"))
      (node (ref "SW91") (pin "VCC") (pinfunction "VCC_VCC") (pintype "unspecified"))
      (node (ref "SW92") (pin "VCC") (pinfunction "VCC_VCC") (pintype "unspecified"))
      (node (ref "SW93") (pin "VCC") (pinfunction "VCC_VCC") (pintype "unspecified"))
      (node (ref "SW94") (pin "VCC") (pinfunction "VCC_VCC") (pintype "unspecified"))
      (node (ref "SW95") (pin "VCC") (pinfunction "VCC_VCC") (pintype "unspecified"))
      (node (ref "SW96") (pin "VCC") (pinfunction "VCC_VCC") (pintype "unspecified"))
      (node (ref "SW97") (pin "VCC") (pinfunction "VCC_VCC") (pintype "unspecified"))
      (node (ref "SW98") (pin "VCC") (pinfunction "VCC_VCC") (pintype "unspecified"))
      (node (ref "SW99") (pin "VCC") (pinfunction "VCC_VCC") (pintype "unspecified"))
      (node (ref "U1") (pin "18") (pinfunction "VDD_18") (pintype "unspecified"))
      (node (ref "U1") (pin "46") (pinfunction "VDD_46") (pintype "unspecified"))
      (node (ref "U10") (pin "18") (pinfunction "VDD_18") (pintype "unspecified"))
      (node (ref "U10") (pin "46") (pinfunction "VDD_46") (pintype "unspecified"))
      (node (ref "U11") (pin "2") (pinfunction "2_2") (pintype "unspecified"))
      (node (ref "U14") (pin "2") (pinfunction "2_2") (pintype "unspecified"))
      (node (ref "U15") (pin "2") (pinfunction "2_2") (pintype "unspecified"))
      (node (ref "U18") (pin "2") (pinfunction "2_2") (pintype "unspecified"))
      (node (ref "U19") (pin "2") (pinfunction "2_2") (pintype "unspecified"))
      (node (ref "U22") (pin "2") (pinfunction "2_2") (pintype "unspecified"))
      (node (ref "U23") (pin "18") (pinfunction "VDD_18") (pintype "unspecified"))
      (node (ref "U23") (pin "46") (pinfunction "VDD_46") (pintype "unspecified"))
      (node (ref "U3") (pin "14") (pinfunction "5V_14") (pintype "unspecified"))
      (node (ref "U5") (pin "2") (pinfunction "2_2") (pintype "unspecified"))
      (node (ref "U6") (pin "2") (pinfunction "2_2") (pintype "unspecified"))
      (node (ref "U9") (pin "2") (pinfunction "2_2") (pintype "unspecified"))
    )
    (net (code "248") (name "VSS_PCA") (class "Default")
      (node (ref "C1") (pin "2") (pinfunction "2_2") (pintype "unspecified"))
      (node (ref "C2") (pin "2") (pinfunction "2_2") (pintype "unspecified"))
      (node (ref "C3") (pin "2") (pinfunction "2_2") (pintype "unspecified"))
      (node (ref "C4") (pin "2") (pinfunction "2_2") (pintype "unspecified"))
      (node (ref "C5") (pin "2") (pinfunction "2_2") (pintype "unspecified"))
      (node (ref "C6") (pin "2") (pinfunction "2_2") (pintype "unspecified"))
      (node (ref "H1") (pin "6") (pinfunction "6_6") (pintype "unspecified"))
      (node (ref "H9") (pin "3") (pinfunction "3_3") (pintype "unspecified"))
      (node (ref "SW0") (pin "GND") (pinfunction "GND_GND") (pintype "unspecified"))
      (node (ref "SW0") (pin "SW2") (pinfunction "SW2_SW2") (pintype "unspecified"))
      (node (ref "SW1") (pin "GND") (pinfunction "GND_GND") (pintype "unspecified"))
      (node (ref "SW1") (pin "SW2") (pinfunction "SW2_SW2") (pintype "unspecified"))
      (node (ref "SW10") (pin "GND") (pinfunction "GND_GND") (pintype "unspecified"))
      (node (ref "SW10") (pin "SW2") (pinfunction "SW2_SW2") (pintype "unspecified"))
      (node (ref "SW100") (pin "GND") (pinfunction "GND_GND") (pintype "unspecified"))
      (node (ref "SW100") (pin "SW2") (pinfunction "SW2_SW2") (pintype "unspecified"))
      (node (ref "SW101") (pin "GND") (pinfunction "GND_GND") (pintype "unspecified"))
      (node (ref "SW101") (pin "SW2") (pinfunction "SW2_SW2") (pintype "unspecified"))
      (node (ref "SW102") (pin "GND") (pinfunction "GND_GND") (pintype "unspecified"))
      (node (ref "SW102") (pin "SW2") (pinfunction "SW2_SW2") (pintype "unspecified"))
      (node (ref "SW104") (pin "GND") (pinfunction "GND_GND") (pintype "unspecified"))
      (node (ref "SW104") (pin "SW2") (pinfunction "SW2_SW2") (pintype "unspecified"))
      (node (ref "SW11") (pin "GND") (pinfunction "GND_GND") (pintype "unspecified"))
      (node (ref "SW11") (pin "SW2") (pinfunction "SW2_SW2") (pintype "unspecified"))
      (node (ref "SW12") (pin "GND") (pinfunction "GND_GND") (pintype "unspecified"))
      (node (ref "SW12") (pin "SW2") (pinfunction "SW2_SW2") (pintype "unspecified"))
      (node (ref "SW13") (pin "GND") (pinfunction "GND_GND") (pintype "unspecified"))
      (node (ref "SW13") (pin "SW2") (pinfunction "SW2_SW2") (pintype "unspecified"))
      (node (ref "SW14") (pin "GND") (pinfunction "GND_GND") (pintype "unspecified"))
      (node (ref "SW14") (pin "SW2") (pinfunction "SW2_SW2") (pintype "unspecified"))
      (node (ref "SW15") (pin "GND") (pinfunction "GND_GND") (pintype "unspecified"))
      (node (ref "SW15") (pin "SW2") (pinfunction "SW2_SW2") (pintype "unspecified"))
      (node (ref "SW16") (pin "GND") (pinfunction "GND_GND") (pintype "unspecified"))
      (node (ref "SW16") (pin "SW2") (pinfunction "SW2_SW2") (pintype "unspecified"))
      (node (ref "SW17") (pin "GND") (pinfunction "GND_GND") (pintype "unspecified"))
      (node (ref "SW17") (pin "SW2") (pinfunction "SW2_SW2") (pintype "unspecified"))
      (node (ref "SW18") (pin "GND") (pinfunction "GND_GND") (pintype "unspecified"))
      (node (ref "SW18") (pin "SW2") (pinfunction "SW2_SW2") (pintype "unspecified"))
      (node (ref "SW19") (pin "GND") (pinfunction "GND_GND") (pintype "unspecified"))
      (node (ref "SW19") (pin "SW2") (pinfunction "SW2_SW2") (pintype "unspecified"))
      (node (ref "SW2") (pin "GND") (pinfunction "GND_GND") (pintype "unspecified"))
      (node (ref "SW2") (pin "SW2") (pinfunction "SW2_SW2") (pintype "unspecified"))
      (node (ref "SW20") (pin "GND") (pinfunction "GND_GND") (pintype "unspecified"))
      (node (ref "SW20") (pin "SW2") (pinfunction "SW2_SW2") (pintype "unspecified"))
      (node (ref "SW21") (pin "GND") (pinfunction "GND_GND") (pintype "unspecified"))
      (node (ref "SW21") (pin "SW2") (pinfunction "SW2_SW2") (pintype "unspecified"))
      (node (ref "SW22") (pin "GND") (pinfunction "GND_GND") (pintype "unspecified"))
      (node (ref "SW22") (pin "SW2") (pinfunction "SW2_SW2") (pintype "unspecified"))
      (node (ref "SW23") (pin "GND") (pinfunction "GND_GND") (pintype "unspecified"))
      (node (ref "SW23") (pin "SW2") (pinfunction "SW2_SW2") (pintype "unspecified"))
      (node (ref "SW24") (pin "GND") (pinfunction "GND_GND") (pintype "unspecified"))
      (node (ref "SW24") (pin "SW2") (pinfunction "SW2_SW2") (pintype "unspecified"))
      (node (ref "SW25") (pin "GND") (pinfunction "GND_GND") (pintype "unspecified"))
      (node (ref "SW25") (pin "SW2") (pinfunction "SW2_SW2") (pintype "unspecified"))
      (node (ref "SW26") (pin "GND") (pinfunction "GND_GND") (pintype "unspecified"))
      (node (ref "SW26") (pin "SW2") (pinfunction "SW2_SW2") (pintype "unspecified"))
      (node (ref "SW28") (pin "GND") (pinfunction "GND_GND") (pintype "unspecified"))
      (node (ref "SW28") (pin "SW2") (pinfunction "SW2_SW2") (pintype "unspecified"))
      (node (ref "SW29") (pin "GND") (pinfunction "GND_GND") (pintype "unspecified"))
      (node (ref "SW29") (pin "SW2") (pinfunction "SW2_SW2") (pintype "unspecified"))
      (node (ref "SW3") (pin "GND") (pinfunction "GND_GND") (pintype "unspecified"))
      (node (ref "SW3") (pin "SW2") (pinfunction "SW2_SW2") (pintype "unspecified"))
      (node (ref "SW31") (pin "GND") (pinfunction "GND_GND") (pintype "unspecified"))
      (node (ref "SW31") (pin "SW2") (pinfunction "SW2_SW2") (pintype "unspecified"))
      (node (ref "SW32") (pin "GND") (pinfunction "GND_GND") (pintype "unspecified"))
      (node (ref "SW32") (pin "SW2") (pinfunction "SW2_SW2") (pintype "unspecified"))
      (node (ref "SW33") (pin "GND") (pinfunction "GND_GND") (pintype "unspecified"))
      (node (ref "SW33") (pin "SW2") (pinfunction "SW2_SW2") (pintype "unspecified"))
      (node (ref "SW34") (pin "GND") (pinfunction "GND_GND") (pintype "unspecified"))
      (node (ref "SW34") (pin "SW2") (pinfunction "SW2_SW2") (pintype "unspecified"))
      (node (ref "SW35") (pin "GND") (pinfunction "GND_GND") (pintype "unspecified"))
      (node (ref "SW35") (pin "SW2") (pinfunction "SW2_SW2") (pintype "unspecified"))
      (node (ref "SW36") (pin "GND") (pinfunction "GND_GND") (pintype "unspecified"))
      (node (ref "SW36") (pin "SW2") (pinfunction "SW2_SW2") (pintype "unspecified"))
      (node (ref "SW37") (pin "GND") (pinfunction "GND_GND") (pintype "unspecified"))
      (node (ref "SW37") (pin "SW2") (pinfunction "SW2_SW2") (pintype "unspecified"))
      (node (ref "SW38") (pin "GND") (pinfunction "GND_GND") (pintype "unspecified"))
      (node (ref "SW38") (pin "SW2") (pinfunction "SW2_SW2") (pintype "unspecified"))
      (node (ref "SW4") (pin "GND") (pinfunction "GND_GND") (pintype "unspecified"))
      (node (ref "SW4") (pin "SW2") (pinfunction "SW2_SW2") (pintype "unspecified"))
      (node (ref "SW40") (pin "GND") (pinfunction "GND_GND") (pintype "unspecified"))
      (node (ref "SW40") (pin "SW2") (pinfunction "SW2_SW2") (pintype "unspecified"))
      (node (ref "SW41") (pin "GND") (pinfunction "GND_GND") (pintype "unspecified"))
      (node (ref "SW41") (pin "SW2") (pinfunction "SW2_SW2") (pintype "unspecified"))
      (node (ref "SW42") (pin "GND") (pinfunction "GND_GND") (pintype "unspecified"))
      (node (ref "SW42") (pin "SW2") (pinfunction "SW2_SW2") (pintype "unspecified"))
      (node (ref "SW43") (pin "GND") (pinfunction "GND_GND") (pintype "unspecified"))
      (node (ref "SW43") (pin "SW2") (pinfunction "SW2_SW2") (pintype "unspecified"))
      (node (ref "SW44") (pin "GND") (pinfunction "GND_GND") (pintype "unspecified"))
      (node (ref "SW44") (pin "SW2") (pinfunction "SW2_SW2") (pintype "unspecified"))
      (node (ref "SW45") (pin "GND") (pinfunction "GND_GND") (pintype "unspecified"))
      (node (ref "SW45") (pin "SW2") (pinfunction "SW2_SW2") (pintype "unspecified"))
      (node (ref "SW46") (pin "GND") (pinfunction "GND_GND") (pintype "unspecified"))
      (node (ref "SW46") (pin "SW2") (pinfunction "SW2_SW2") (pintype "unspecified"))
      (node (ref "SW47") (pin "GND") (pinfunction "GND_GND") (pintype "unspecified"))
      (node (ref "SW47") (pin "SW2") (pinfunction "SW2_SW2") (pintype "unspecified"))
      (node (ref "SW48") (pin "GND") (pinfunction "GND_GND") (pintype "unspecified"))
      (node (ref "SW48") (pin "SW2") (pinfunction "SW2_SW2") (pintype "unspecified"))
      (node (ref "SW49") (pin "GND") (pinfunction "GND_GND") (pintype "unspecified"))
      (node (ref "SW49") (pin "SW2") (pinfunction "SW2_SW2") (pintype "unspecified"))
      (node (ref "SW5") (pin "GND") (pinfunction "GND_GND") (pintype "unspecified"))
      (node (ref "SW5") (pin "SW2") (pinfunction "SW2_SW2") (pintype "unspecified"))
      (node (ref "SW50") (pin "GND") (pinfunction "GND_GND") (pintype "unspecified"))
      (node (ref "SW50") (pin "SW2") (pinfunction "SW2_SW2") (pintype "unspecified"))
      (node (ref "SW52") (pin "GND") (pinfunction "GND_GND") (pintype "unspecified"))
      (node (ref "SW52") (pin "SW2") (pinfunction "SW2_SW2") (pintype "unspecified"))
      (node (ref "SW53") (pin "GND") (pinfunction "GND_GND") (pintype "unspecified"))
      (node (ref "SW53") (pin "SW2") (pinfunction "SW2_SW2") (pintype "unspecified"))
      (node (ref "SW55") (pin "GND") (pinfunction "GND_GND") (pintype "unspecified"))
      (node (ref "SW55") (pin "SW2") (pinfunction "SW2_SW2") (pintype "unspecified"))
      (node (ref "SW56") (pin "GND") (pinfunction "GND_GND") (pintype "unspecified"))
      (node (ref "SW56") (pin "SW2") (pinfunction "SW2_SW2") (pintype "unspecified"))
      (node (ref "SW57") (pin "GND") (pinfunction "GND_GND") (pintype "unspecified"))
      (node (ref "SW57") (pin "SW2") (pinfunction "SW2_SW2") (pintype "unspecified"))
      (node (ref "SW58") (pin "GND") (pinfunction "GND_GND") (pintype "unspecified"))
      (node (ref "SW58") (pin "SW2") (pinfunction "SW2_SW2") (pintype "unspecified"))
      (node (ref "SW59") (pin "GND") (pinfunction "GND_GND") (pintype "unspecified"))
      (node (ref "SW59") (pin "SW2") (pinfunction "SW2_SW2") (pintype "unspecified"))
      (node (ref "SW6") (pin "GND") (pinfunction "GND_GND") (pintype "unspecified"))
      (node (ref "SW6") (pin "SW2") (pinfunction "SW2_SW2") (pintype "unspecified"))
      (node (ref "SW60") (pin "GND") (pinfunction "GND_GND") (pintype "unspecified"))
      (node (ref "SW60") (pin "SW2") (pinfunction "SW2_SW2") (pintype "unspecified"))
      (node (ref "SW61") (pin "GND") (pinfunction "GND_GND") (pintype "unspecified"))
      (node (ref "SW61") (pin "SW2") (pinfunction "SW2_SW2") (pintype "unspecified"))
      (node (ref "SW62") (pin "GND") (pinfunction "GND_GND") (pintype "unspecified"))
      (node (ref "SW62") (pin "SW2") (pinfunction "SW2_SW2") (pintype "unspecified"))
      (node (ref "SW64") (pin "GND") (pinfunction "GND_GND") (pintype "unspecified"))
      (node (ref "SW64") (pin "SW2") (pinfunction "SW2_SW2") (pintype "unspecified"))
      (node (ref "SW65") (pin "GND") (pinfunction "GND_GND") (pintype "unspecified"))
      (node (ref "SW65") (pin "SW2") (pinfunction "SW2_SW2") (pintype "unspecified"))
      (node (ref "SW66") (pin "GND") (pinfunction "GND_GND") (pintype "unspecified"))
      (node (ref "SW66") (pin "SW2") (pinfunction "SW2_SW2") (pintype "unspecified"))
      (node (ref "SW67") (pin "GND") (pinfunction "GND_GND") (pintype "unspecified"))
      (node (ref "SW67") (pin "SW2") (pinfunction "SW2_SW2") (pintype "unspecified"))
      (node (ref "SW68") (pin "GND") (pinfunction "GND_GND") (pintype "unspecified"))
      (node (ref "SW68") (pin "SW2") (pinfunction "SW2_SW2") (pintype "unspecified"))
      (node (ref "SW69") (pin "GND") (pinfunction "GND_GND") (pintype "unspecified"))
      (node (ref "SW69") (pin "SW2") (pinfunction "SW2_SW2") (pintype "unspecified"))
      (node (ref "SW7") (pin "GND") (pinfunction "GND_GND") (pintype "unspecified"))
      (node (ref "SW7") (pin "SW2") (pinfunction "SW2_SW2") (pintype "unspecified"))
      (node (ref "SW70") (pin "GND") (pinfunction "GND_GND") (pintype "unspecified"))
      (node (ref "SW70") (pin "SW2") (pinfunction "SW2_SW2") (pintype "unspecified"))
      (node (ref "SW71") (pin "GND") (pinfunction "GND_GND") (pintype "unspecified"))
      (node (ref "SW71") (pin "SW2") (pinfunction "SW2_SW2") (pintype "unspecified"))
      (node (ref "SW72") (pin "GND") (pinfunction "GND_GND") (pintype "unspecified"))
      (node (ref "SW72") (pin "SW2") (pinfunction "SW2_SW2") (pintype "unspecified"))
      (node (ref "SW73") (pin "GND") (pinfunction "GND_GND") (pintype "unspecified"))
      (node (ref "SW73") (pin "SW2") (pinfunction "SW2_SW2") (pintype "unspecified"))
      (node (ref "SW74") (pin "GND") (pinfunction "GND_GND") (pintype "unspecified"))
      (node (ref "SW74") (pin "SW2") (pinfunction "SW2_SW2") (pintype "unspecified"))
      (node (ref "SW75") (pin "GND") (pinfunction "GND_GND") (pintype "unspecified"))
      (node (ref "SW75") (pin "SW2") (pinfunction "SW2_SW2") (pintype "unspecified"))
      (node (ref "SW76") (pin "GND") (pinfunction "GND_GND") (pintype "unspecified"))
      (node (ref "SW76") (pin "SW2") (pinfunction "SW2_SW2") (pintype "unspecified"))
      (node (ref "SW78") (pin "GND") (pinfunction "GND_GND") (pintype "unspecified"))
      (node (ref "SW78") (pin "SW2") (pinfunction "SW2_SW2") (pintype "unspecified"))
      (node (ref "SW8") (pin "GND") (pinfunction "GND_GND") (pintype "unspecified"))
      (node (ref "SW8") (pin "SW2") (pinfunction "SW2_SW2") (pintype "unspecified"))
      (node (ref "SW80") (pin "GND") (pinfunction "GND_GND") (pintype "unspecified"))
      (node (ref "SW80") (pin "SW2") (pinfunction "SW2_SW2") (pintype "unspecified"))
      (node (ref "SW81") (pin "GND") (pinfunction "GND_GND") (pintype "unspecified"))
      (node (ref "SW81") (pin "SW2") (pinfunction "SW2_SW2") (pintype "unspecified"))
      (node (ref "SW82") (pin "GND") (pinfunction "GND_GND") (pintype "unspecified"))
      (node (ref "SW82") (pin "SW2") (pinfunction "SW2_SW2") (pintype "unspecified"))
      (node (ref "SW83") (pin "GND") (pinfunction "GND_GND") (pintype "unspecified"))
      (node (ref "SW83") (pin "SW2") (pinfunction "SW2_SW2") (pintype "unspecified"))
      (node (ref "SW84") (pin "GND") (pinfunction "GND_GND") (pintype "unspecified"))
      (node (ref "SW84") (pin "SW2") (pinfunction "SW2_SW2") (pintype "unspecified"))
      (node (ref "SW85") (pin "GND") (pinfunction "GND_GND") (pintype "unspecified"))
      (node (ref "SW85") (pin "SW2") (pinfunction "SW2_SW2") (pintype "unspecified"))
      (node (ref "SW86") (pin "GND") (pinfunction "GND_GND") (pintype "unspecified"))
      (node (ref "SW86") (pin "SW2") (pinfunction "SW2_SW2") (pintype "unspecified"))
      (node (ref "SW87") (pin "GND") (pinfunction "GND_GND") (pintype "unspecified"))
      (node (ref "SW87") (pin "SW2") (pinfunction "SW2_SW2") (pintype "unspecified"))
      (node (ref "SW88") (pin "GND") (pinfunction "GND_GND") (pintype "unspecified"))
      (node (ref "SW88") (pin "SW2") (pinfunction "SW2_SW2") (pintype "unspecified"))
      (node (ref "SW89") (pin "GND") (pinfunction "GND_GND") (pintype "unspecified"))
      (node (ref "SW89") (pin "SW2") (pinfunction "SW2_SW2") (pintype "unspecified"))
      (node (ref "SW9") (pin "GND") (pinfunction "GND_GND") (pintype "unspecified"))
      (node (ref "SW9") (pin "SW2") (pinfunction "SW2_SW2") (pintype "unspecified"))
      (node (ref "SW91") (pin "GND") (pinfunction "GND_GND") (pintype "unspecified"))
      (node (ref "SW91") (pin "SW2") (pinfunction "SW2_SW2") (pintype "unspecified"))
      (node (ref "SW92") (pin "GND") (pinfunction "GND_GND") (pintype "unspecified"))
      (node (ref "SW92") (pin "SW2") (pinfunction "SW2_SW2") (pintype "unspecified"))
      (node (ref "SW93") (pin "GND") (pinfunction "GND_GND") (pintype "unspecified"))
      (node (ref "SW93") (pin "SW2") (pinfunction "SW2_SW2") (pintype "unspecified"))
      (node (ref "SW94") (pin "GND") (pinfunction "GND_GND") (pintype "unspecified"))
      (node (ref "SW94") (pin "SW2") (pinfunction "SW2_SW2") (pintype "unspecified"))
      (node (ref "SW95") (pin "GND") (pinfunction "GND_GND") (pintype "unspecified"))
      (node (ref "SW95") (pin "SW2") (pinfunction "SW2_SW2") (pintype "unspecified"))
      (node (ref "SW96") (pin "GND") (pinfunction "GND_GND") (pintype "unspecified"))
      (node (ref "SW96") (pin "SW2") (pinfunction "SW2_SW2") (pintype "unspecified"))
      (node (ref "SW97") (pin "GND") (pinfunction "GND_GND") (pintype "unspecified"))
      (node (ref "SW97") (pin "SW2") (pinfunction "SW2_SW2") (pintype "unspecified"))
      (node (ref "SW98") (pin "GND") (pinfunction "GND_GND") (pintype "unspecified"))
      (node (ref "SW98") (pin "SW2") (pinfunction "SW2_SW2") (pintype "unspecified"))
      (node (ref "SW99") (pin "GND") (pinfunction "GND_GND") (pintype "unspecified"))
      (node (ref "SW99") (pin "SW2") (pinfunction "SW2_SW2") (pintype "unspecified"))
      (node (ref "U1") (pin "11") (pinfunction "VSS_11") (pintype "unspecified"))
      (node (ref "U1") (pin "23") (pinfunction "VSS_23") (pintype "unspecified"))
      (node (ref "U1") (pin "34") (pinfunction "VSS_34") (pintype "unspecified"))
      (node (ref "U1") (pin "39") (pinfunction "VSS_39") (pintype "unspecified"))
      (node (ref "U1") (pin "51") (pinfunction "VSS_51") (pintype "unspecified"))
      (node (ref "U1") (pin "6") (pinfunction "VSS_6") (pintype "unspecified"))
      (node (ref "U10") (pin "11") (pinfunction "VSS_11") (pintype "unspecified"))
      (node (ref "U10") (pin "23") (pinfunction "VSS_23") (pintype "unspecified"))
      (node (ref "U10") (pin "34") (pinfunction "VSS_34") (pintype "unspecified"))
      (node (ref "U10") (pin "39") (pinfunction "VSS_39") (pintype "unspecified"))
      (node (ref "U10") (pin "51") (pinfunction "VSS_51") (pintype "unspecified"))
      (node (ref "U10") (pin "6") (pinfunction "VSS_6") (pintype "unspecified"))
      (node (ref "U12") (pin "2") (pinfunction "2_2") (pintype "unspecified"))
      (node (ref "U13") (pin "2") (pinfunction "2_2") (pintype "unspecified"))
      (node (ref "U16") (pin "2") (pinfunction "2_2") (pintype "unspecified"))
      (node (ref "U17") (pin "2") (pinfunction "2_2") (pintype "unspecified"))
      (node (ref "U20") (pin "2") (pinfunction "2_2") (pintype "unspecified"))
      (node (ref "U21") (pin "2") (pinfunction "2_2") (pintype "unspecified"))
      (node (ref "U23") (pin "11") (pinfunction "VSS_11") (pintype "unspecified"))
      (node (ref "U23") (pin "23") (pinfunction "VSS_23") (pintype "unspecified"))
      (node (ref "U23") (pin "34") (pinfunction "VSS_34") (pintype "unspecified"))
      (node (ref "U23") (pin "39") (pinfunction "VSS_39") (pintype "unspecified"))
      (node (ref "U23") (pin "51") (pinfunction "VSS_51") (pintype "unspecified"))
      (node (ref "U23") (pin "6") (pinfunction "VSS_6") (pintype "unspecified"))
      (node (ref "U3") (pin "13") (pinfunction "GND_13") (pintype "unspecified"))
      (node (ref "U3") (pin "22") (pinfunction "GND_22") (pintype "unspecified"))
      (node (ref "U4") (pin "2") (pinfunction "2_2") (pintype "unspecified"))
      (node (ref "U7") (pin "2") (pinfunction "2_2") (pintype "unspecified"))
      (node (ref "U8") (pin "2") (pinfunction "2_2") (pintype "unspecified"))
    )
    (net (code "249") (name "unconnected-(U3-BAT-Pad21)") (class "Default")
      (node (ref "U3") (pin "21") (pinfunction "BAT_21") (pintype "unspecified"))
    )
    (net (code "250") (name "unconnected-(U3-RST-Pad23)") (class "Default")
      (node (ref "U3") (pin "23") (pinfunction "RST_23") (pintype "unspecified"))
    )
  )
)
